# 2_waffling80-MX_matrix.net
KiCad netlist of a schematic drawn in Altium Designer
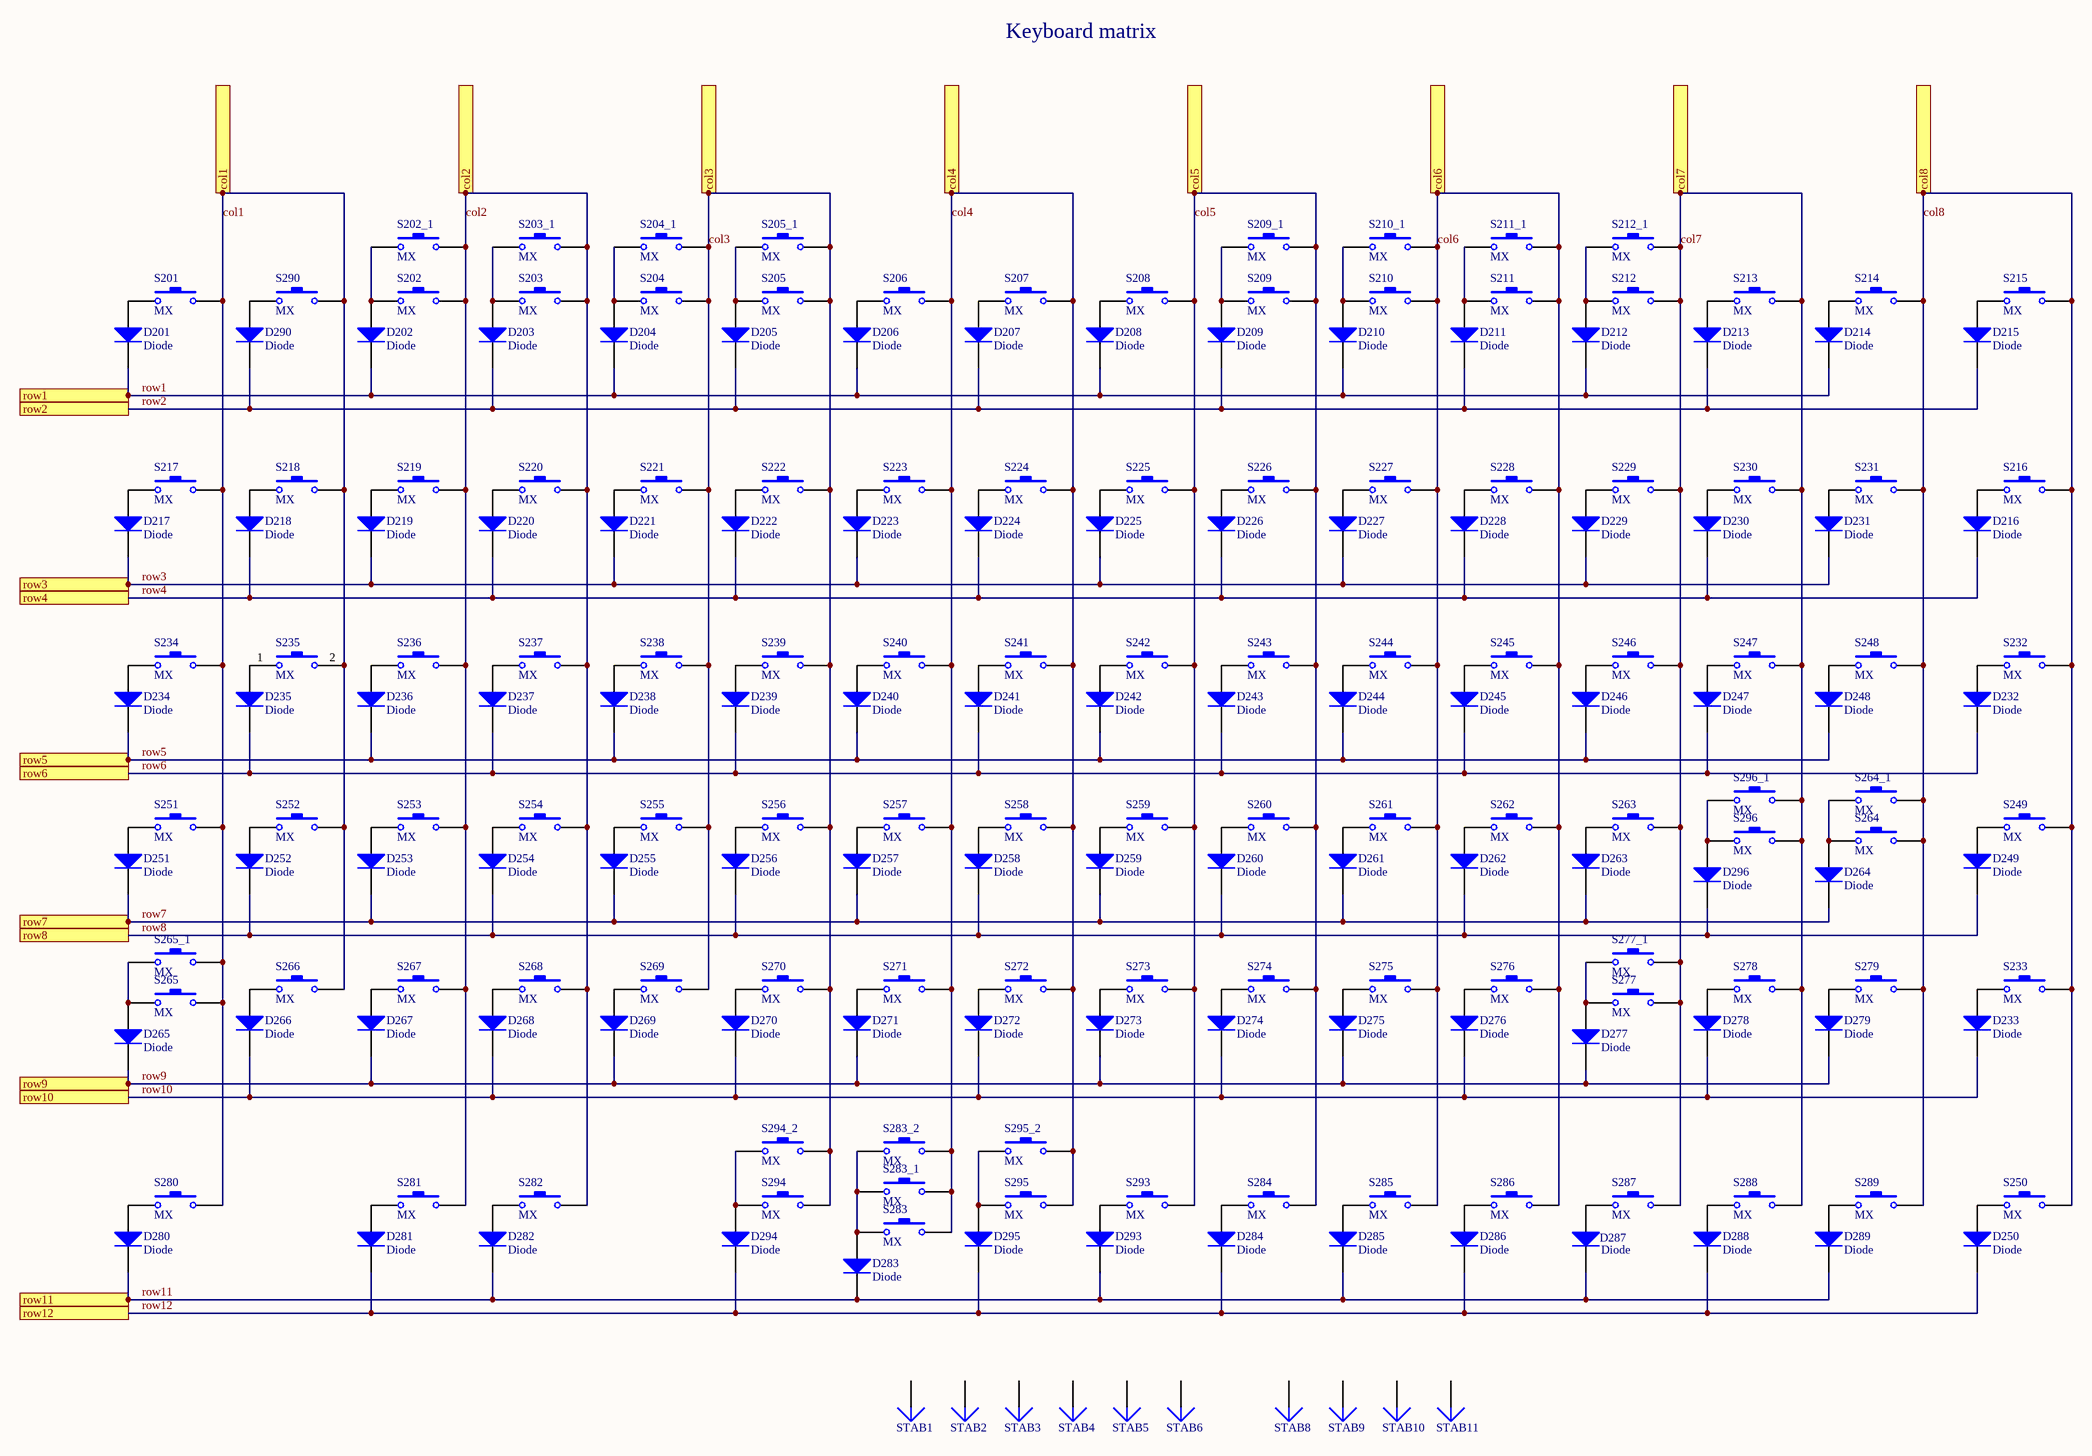
[diagram p0: 2_waffling80-MX_matrix.SchDoc]

(export (version "E")
  (design (tool "Eeschema 10.0.6"))
  (components
    (comp (ref "D201")
      (value "Diode")
      (footprint "SOD-123")
      (description "Default Diode")
      (fields (field (name "LCSC PART #") "C81598") (field (name "MRF.PART") "1N4148W"))
      (libsource (lib "Miscellaneous Devices") (part "Diode"))
    )
    (comp (ref "D202")
      (value "Diode")
      (footprint "SOD-123")
      (description "Default Diode")
      (fields (field (name "LCSC PART #") "C81598") (field (name "MRF.PART") "1N4148W"))
      (libsource (lib "Miscellaneous Devices") (part "Diode"))
    )
    (comp (ref "D203")
      (value "Diode")
      (footprint "SOD-123")
      (description "Default Diode")
      (fields (field (name "LCSC PART #") "C81598") (field (name "MRF.PART") "1N4148W"))
      (libsource (lib "Miscellaneous Devices") (part "Diode"))
    )
    (comp (ref "D204")
      (value "Diode")
      (footprint "SOD-123")
      (description "Default Diode")
      (fields (field (name "LCSC PART #") "C81598") (field (name "MRF.PART") "1N4148W"))
      (libsource (lib "Miscellaneous Devices") (part "Diode"))
    )
    (comp (ref "D205")
      (value "Diode")
      (footprint "SOD-123")
      (description "Default Diode")
      (fields (field (name "LCSC PART #") "C81598") (field (name "MRF.PART") "1N4148W"))
      (libsource (lib "Miscellaneous Devices") (part "Diode"))
    )
    (comp (ref "D206")
      (value "Diode")
      (footprint "SOD-123")
      (description "Default Diode")
      (fields (field (name "LCSC PART #") "C81598") (field (name "MRF.PART") "1N4148W"))
      (libsource (lib "Miscellaneous Devices") (part "Diode"))
    )
    (comp (ref "D207")
      (value "Diode")
      (footprint "SOD-123")
      (description "Default Diode")
      (fields (field (name "LCSC PART #") "C81598") (field (name "MRF.PART") "1N4148W"))
      (libsource (lib "Miscellaneous Devices") (part "Diode"))
    )
    (comp (ref "D208")
      (value "Diode")
      (footprint "SOD-123")
      (description "Default Diode")
      (fields (field (name "LCSC PART #") "C81598") (field (name "MRF.PART") "1N4148W"))
      (libsource (lib "Miscellaneous Devices") (part "Diode"))
    )
    (comp (ref "D209")
      (value "Diode")
      (footprint "SOD-123")
      (description "Default Diode")
      (fields (field (name "LCSC PART #") "C81598") (field (name "MRF.PART") "1N4148W"))
      (libsource (lib "Miscellaneous Devices") (part "Diode"))
    )
    (comp (ref "D210")
      (value "Diode")
      (footprint "SOD-123")
      (description "Default Diode")
      (fields (field (name "LCSC PART #") "C81598") (field (name "MRF.PART") "1N4148W"))
      (libsource (lib "Miscellaneous Devices") (part "Diode"))
    )
    (comp (ref "D211")
      (value "Diode")
      (footprint "SOD-123")
      (description "Default Diode")
      (fields (field (name "LCSC PART #") "C81598") (field (name "MRF.PART") "1N4148W"))
      (libsource (lib "Miscellaneous Devices") (part "Diode"))
    )
    (comp (ref "D212")
      (value "Diode")
      (footprint "SOD-123")
      (description "Default Diode")
      (fields (field (name "LCSC PART #") "C81598") (field (name "MRF.PART") "1N4148W"))
      (libsource (lib "Miscellaneous Devices") (part "Diode"))
    )
    (comp (ref "D213")
      (value "Diode")
      (footprint "SOD-123")
      (description "Default Diode")
      (fields (field (name "LCSC PART #") "C81598") (field (name "MRF.PART") "1N4148W"))
      (libsource (lib "Miscellaneous Devices") (part "Diode"))
    )
    (comp (ref "D214")
      (value "Diode")
      (footprint "SOD-123")
      (description "Default Diode")
      (fields (field (name "LCSC PART #") "C81598") (field (name "MRF.PART") "1N4148W"))
      (libsource (lib "Miscellaneous Devices") (part "Diode"))
    )
    (comp (ref "D215")
      (value "Diode")
      (footprint "SOD-123")
      (description "Default Diode")
      (fields (field (name "LCSC PART #") "C81598") (field (name "MRF.PART") "1N4148W"))
      (libsource (lib "Miscellaneous Devices") (part "Diode"))
    )
    (comp (ref "D216")
      (value "Diode")
      (footprint "SOD-123")
      (description "Default Diode")
      (fields (field (name "LCSC PART #") "C81598") (field (name "MRF.PART") "1N4148W"))
      (libsource (lib "Miscellaneous Devices") (part "Diode"))
    )
    (comp (ref "D217")
      (value "Diode")
      (footprint "SOD-123")
      (description "Default Diode")
      (fields (field (name "LCSC PART #") "C81598") (field (name "MRF.PART") "1N4148W"))
      (libsource (lib "Miscellaneous Devices") (part "Diode"))
    )
    (comp (ref "D218")
      (value "Diode")
      (footprint "SOD-123")
      (description "Default Diode")
      (fields (field (name "LCSC PART #") "C81598") (field (name "MRF.PART") "1N4148W"))
      (libsource (lib "Miscellaneous Devices") (part "Diode"))
    )
    (comp (ref "D219")
      (value "Diode")
      (footprint "SOD-123")
      (description "Default Diode")
      (fields (field (name "LCSC PART #") "C81598") (field (name "MRF.PART") "1N4148W"))
      (libsource (lib "Miscellaneous Devices") (part "Diode"))
    )
    (comp (ref "D220")
      (value "Diode")
      (footprint "SOD-123")
      (description "Default Diode")
      (fields (field (name "LCSC PART #") "C81598") (field (name "MRF.PART") "1N4148W"))
      (libsource (lib "Miscellaneous Devices") (part "Diode"))
    )
    (comp (ref "D221")
      (value "Diode")
      (footprint "SOD-123")
      (description "Default Diode")
      (fields (field (name "LCSC PART #") "C81598") (field (name "MRF.PART") "1N4148W"))
      (libsource (lib "Miscellaneous Devices") (part "Diode"))
    )
    (comp (ref "D222")
      (value "Diode")
      (footprint "SOD-123")
      (description "Default Diode")
      (fields (field (name "LCSC PART #") "C81598") (field (name "MRF.PART") "1N4148W"))
      (libsource (lib "Miscellaneous Devices") (part "Diode"))
    )
    (comp (ref "D223")
      (value "Diode")
      (footprint "SOD-123")
      (description "Default Diode")
      (fields (field (name "LCSC PART #") "C81598") (field (name "MRF.PART") "1N4148W"))
      (libsource (lib "Miscellaneous Devices") (part "Diode"))
    )
    (comp (ref "D224")
      (value "Diode")
      (footprint "SOD-123")
      (description "Default Diode")
      (fields (field (name "LCSC PART #") "C81598") (field (name "MRF.PART") "1N4148W"))
      (libsource (lib "Miscellaneous Devices") (part "Diode"))
    )
    (comp (ref "D225")
      (value "Diode")
      (footprint "SOD-123")
      (description "Default Diode")
      (fields (field (name "LCSC PART #") "C81598") (field (name "MRF.PART") "1N4148W"))
      (libsource (lib "Miscellaneous Devices") (part "Diode"))
    )
    (comp (ref "D226")
      (value "Diode")
      (footprint "SOD-123")
      (description "Default Diode")
      (fields (field (name "LCSC PART #") "C81598") (field (name "MRF.PART") "1N4148W"))
      (libsource (lib "Miscellaneous Devices") (part "Diode"))
    )
    (comp (ref "D227")
      (value "Diode")
      (footprint "SOD-123")
      (description "Default Diode")
      (fields (field (name "LCSC PART #") "C81598") (field (name "MRF.PART") "1N4148W"))
      (libsource (lib "Miscellaneous Devices") (part "Diode"))
    )
    (comp (ref "D228")
      (value "Diode")
      (footprint "SOD-123")
      (description "Default Diode")
      (fields (field (name "LCSC PART #") "C81598") (field (name "MRF.PART") "1N4148W"))
      (libsource (lib "Miscellaneous Devices") (part "Diode"))
    )
    (comp (ref "D229")
      (value "Diode")
      (footprint "SOD-123")
      (description "Default Diode")
      (fields (field (name "LCSC PART #") "C81598") (field (name "MRF.PART") "1N4148W"))
      (libsource (lib "Miscellaneous Devices") (part "Diode"))
    )
    (comp (ref "D230")
      (value "Diode")
      (footprint "SOD-123")
      (description "Default Diode")
      (fields (field (name "LCSC PART #") "C81598") (field (name "MRF.PART") "1N4148W"))
      (libsource (lib "Miscellaneous Devices") (part "Diode"))
    )
    (comp (ref "D231")
      (value "Diode")
      (footprint "SOD-123")
      (description "Default Diode")
      (fields (field (name "LCSC PART #") "C81598") (field (name "MRF.PART") "1N4148W"))
      (libsource (lib "Miscellaneous Devices") (part "Diode"))
    )
    (comp (ref "D232")
      (value "Diode")
      (footprint "SOD-123")
      (description "Default Diode")
      (fields (field (name "LCSC PART #") "C81598") (field (name "MRF.PART") "1N4148W"))
      (libsource (lib "Miscellaneous Devices") (part "Diode"))
    )
    (comp (ref "D233")
      (value "Diode")
      (footprint "SOD-123")
      (description "Default Diode")
      (fields (field (name "LCSC PART #") "C81598") (field (name "MRF.PART") "1N4148W"))
      (libsource (lib "Miscellaneous Devices") (part "Diode"))
    )
    (comp (ref "D234")
      (value "Diode")
      (footprint "SOD-123")
      (description "Default Diode")
      (fields (field (name "LCSC PART #") "C81598") (field (name "MRF.PART") "1N4148W"))
      (libsource (lib "Miscellaneous Devices") (part "Diode"))
    )
    (comp (ref "D235")
      (value "Diode")
      (footprint "SOD-123")
      (description "Default Diode")
      (fields (field (name "LCSC PART #") "C81598") (field (name "MRF.PART") "1N4148W"))
      (libsource (lib "Miscellaneous Devices") (part "Diode"))
    )
    (comp (ref "D236")
      (value "Diode")
      (footprint "SOD-123")
      (description "Default Diode")
      (fields (field (name "LCSC PART #") "C81598") (field (name "MRF.PART") "1N4148W"))
      (libsource (lib "Miscellaneous Devices") (part "Diode"))
    )
    (comp (ref "D237")
      (value "Diode")
      (footprint "SOD-123")
      (description "Default Diode")
      (fields (field (name "LCSC PART #") "C81598") (field (name "MRF.PART") "1N4148W"))
      (libsource (lib "Miscellaneous Devices") (part "Diode"))
    )
    (comp (ref "D238")
      (value "Diode")
      (footprint "SOD-123")
      (description "Default Diode")
      (fields (field (name "LCSC PART #") "C81598") (field (name "MRF.PART") "1N4148W"))
      (libsource (lib "Miscellaneous Devices") (part "Diode"))
    )
    (comp (ref "D239")
      (value "Diode")
      (footprint "SOD-123")
      (description "Default Diode")
      (fields (field (name "LCSC PART #") "C81598") (field (name "MRF.PART") "1N4148W"))
      (libsource (lib "Miscellaneous Devices") (part "Diode"))
    )
    (comp (ref "D240")
      (value "Diode")
      (footprint "SOD-123")
      (description "Default Diode")
      (fields (field (name "LCSC PART #") "C81598") (field (name "MRF.PART") "1N4148W"))
      (libsource (lib "Miscellaneous Devices") (part "Diode"))
    )
    (comp (ref "D241")
      (value "Diode")
      (footprint "SOD-123")
      (description "Default Diode")
      (fields (field (name "LCSC PART #") "C81598") (field (name "MRF.PART") "1N4148W"))
      (libsource (lib "Miscellaneous Devices") (part "Diode"))
    )
    (comp (ref "D242")
      (value "Diode")
      (footprint "SOD-123")
      (description "Default Diode")
      (fields (field (name "LCSC PART #") "C81598") (field (name "MRF.PART") "1N4148W"))
      (libsource (lib "Miscellaneous Devices") (part "Diode"))
    )
    (comp (ref "D243")
      (value "Diode")
      (footprint "SOD-123")
      (description "Default Diode")
      (fields (field (name "LCSC PART #") "C81598") (field (name "MRF.PART") "1N4148W"))
      (libsource (lib "Miscellaneous Devices") (part "Diode"))
    )
    (comp (ref "D244")
      (value "Diode")
      (footprint "SOD-123")
      (description "Default Diode")
      (fields (field (name "LCSC PART #") "C81598") (field (name "MRF.PART") "1N4148W"))
      (libsource (lib "Miscellaneous Devices") (part "Diode"))
    )
    (comp (ref "D245")
      (value "Diode")
      (footprint "SOD-123")
      (description "Default Diode")
      (fields (field (name "LCSC PART #") "C81598") (field (name "MRF.PART") "1N4148W"))
      (libsource (lib "Miscellaneous Devices") (part "Diode"))
    )
    (comp (ref "D246")
      (value "Diode")
      (footprint "SOD-123")
      (description "Default Diode")
      (fields (field (name "LCSC PART #") "C81598") (field (name "MRF.PART") "1N4148W"))
      (libsource (lib "Miscellaneous Devices") (part "Diode"))
    )
    (comp (ref "D247")
      (value "Diode")
      (footprint "SOD-123")
      (description "Default Diode")
      (fields (field (name "LCSC PART #") "C81598") (field (name "MRF.PART") "1N4148W"))
      (libsource (lib "Miscellaneous Devices") (part "Diode"))
    )
    (comp (ref "D248")
      (value "Diode")
      (footprint "SOD-123")
      (description "Default Diode")
      (fields (field (name "LCSC PART #") "C81598") (field (name "MRF.PART") "1N4148W"))
      (libsource (lib "Miscellaneous Devices") (part "Diode"))
    )
    (comp (ref "D249")
      (value "Diode")
      (footprint "SOD-123")
      (description "Default Diode")
      (fields (field (name "LCSC PART #") "C81598") (field (name "MRF.PART") "1N4148W"))
      (libsource (lib "Miscellaneous Devices") (part "Diode"))
    )
    (comp (ref "D250")
      (value "Diode")
      (footprint "SOD-123")
      (description "Default Diode")
      (fields (field (name "LCSC PART #") "C81598") (field (name "MRF.PART") "1N4148W"))
      (libsource (lib "Miscellaneous Devices") (part "Diode"))
    )
    (comp (ref "D251")
      (value "Diode")
      (footprint "SOD-123")
      (description "Default Diode")
      (fields (field (name "LCSC PART #") "C81598") (field (name "MRF.PART") "1N4148W"))
      (libsource (lib "Miscellaneous Devices") (part "Diode"))
    )
    (comp (ref "D252")
      (value "Diode")
      (footprint "SOD-123")
      (description "Default Diode")
      (fields (field (name "LCSC PART #") "C81598") (field (name "MRF.PART") "1N4148W"))
      (libsource (lib "Miscellaneous Devices") (part "Diode"))
    )
    (comp (ref "D253")
      (value "Diode")
      (footprint "SOD-123")
      (description "Default Diode")
      (fields (field (name "LCSC PART #") "C81598") (field (name "MRF.PART") "1N4148W"))
      (libsource (lib "Miscellaneous Devices") (part "Diode"))
    )
    (comp (ref "D254")
      (value "Diode")
      (footprint "SOD-123")
      (description "Default Diode")
      (fields (field (name "LCSC PART #") "C81598") (field (name "MRF.PART") "1N4148W"))
      (libsource (lib "Miscellaneous Devices") (part "Diode"))
    )
    (comp (ref "D255")
      (value "Diode")
      (footprint "SOD-123")
      (description "Default Diode")
      (fields (field (name "LCSC PART #") "C81598") (field (name "MRF.PART") "1N4148W"))
      (libsource (lib "Miscellaneous Devices") (part "Diode"))
    )
    (comp (ref "D256")
      (value "Diode")
      (footprint "SOD-123")
      (description "Default Diode")
      (fields (field (name "LCSC PART #") "C81598") (field (name "MRF.PART") "1N4148W"))
      (libsource (lib "Miscellaneous Devices") (part "Diode"))
    )
    (comp (ref "D257")
      (value "Diode")
      (footprint "SOD-123")
      (description "Default Diode")
      (fields (field (name "LCSC PART #") "C81598") (field (name "MRF.PART") "1N4148W"))
      (libsource (lib "Miscellaneous Devices") (part "Diode"))
    )
    (comp (ref "D258")
      (value "Diode")
      (footprint "SOD-123")
      (description "Default Diode")
      (fields (field (name "LCSC PART #") "C81598") (field (name "MRF.PART") "1N4148W"))
      (libsource (lib "Miscellaneous Devices") (part "Diode"))
    )
    (comp (ref "D259")
      (value "Diode")
      (footprint "SOD-123")
      (description "Default Diode")
      (fields (field (name "LCSC PART #") "C81598") (field (name "MRF.PART") "1N4148W"))
      (libsource (lib "Miscellaneous Devices") (part "Diode"))
    )
    (comp (ref "D260")
      (value "Diode")
      (footprint "SOD-123")
      (description "Default Diode")
      (fields (field (name "LCSC PART #") "C81598") (field (name "MRF.PART") "1N4148W"))
      (libsource (lib "Miscellaneous Devices") (part "Diode"))
    )
    (comp (ref "D261")
      (value "Diode")
      (footprint "SOD-123")
      (description "Default Diode")
      (fields (field (name "LCSC PART #") "C81598") (field (name "MRF.PART") "1N4148W"))
      (libsource (lib "Miscellaneous Devices") (part "Diode"))
    )
    (comp (ref "D262")
      (value "Diode")
      (footprint "SOD-123")
      (description "Default Diode")
      (fields (field (name "LCSC PART #") "C81598") (field (name "MRF.PART") "1N4148W"))
      (libsource (lib "Miscellaneous Devices") (part "Diode"))
    )
    (comp (ref "D263")
      (value "Diode")
      (footprint "SOD-123")
      (description "Default Diode")
      (fields (field (name "LCSC PART #") "C81598") (field (name "MRF.PART") "1N4148W"))
      (libsource (lib "Miscellaneous Devices") (part "Diode"))
    )
    (comp (ref "D264")
      (value "Diode")
      (footprint "SOD-123")
      (description "Default Diode")
      (fields (field (name "LCSC PART #") "C81598") (field (name "MRF.PART") "1N4148W"))
      (libsource (lib "Miscellaneous Devices") (part "Diode"))
    )
    (comp (ref "D265")
      (value "Diode")
      (footprint "SOD-123")
      (description "Default Diode")
      (fields (field (name "LCSC PART #") "C81598") (field (name "MRF.PART") "1N4148W"))
      (libsource (lib "Miscellaneous Devices") (part "Diode"))
    )
    (comp (ref "D266")
      (value "Diode")
      (footprint "SOD-123")
      (description "Default Diode")
      (fields (field (name "LCSC PART #") "C81598") (field (name "MRF.PART") "1N4148W"))
      (libsource (lib "Miscellaneous Devices") (part "Diode"))
    )
    (comp (ref "D267")
      (value "Diode")
      (footprint "SOD-123")
      (description "Default Diode")
      (fields (field (name "LCSC PART #") "C81598") (field (name "MRF.PART") "1N4148W"))
      (libsource (lib "Miscellaneous Devices") (part "Diode"))
    )
    (comp (ref "D268")
      (value "Diode")
      (footprint "SOD-123")
      (description "Default Diode")
      (fields (field (name "LCSC PART #") "C81598") (field (name "MRF.PART") "1N4148W"))
      (libsource (lib "Miscellaneous Devices") (part "Diode"))
    )
    (comp (ref "D269")
      (value "Diode")
      (footprint "SOD-123")
      (description "Default Diode")
      (fields (field (name "LCSC PART #") "C81598") (field (name "MRF.PART") "1N4148W"))
      (libsource (lib "Miscellaneous Devices") (part "Diode"))
    )
    (comp (ref "D270")
      (value "Diode")
      (footprint "SOD-123")
      (description "Default Diode")
      (fields (field (name "LCSC PART #") "C81598") (field (name "MRF.PART") "1N4148W"))
      (libsource (lib "Miscellaneous Devices") (part "Diode"))
    )
    (comp (ref "D271")
      (value "Diode")
      (footprint "SOD-123")
      (description "Default Diode")
      (fields (field (name "LCSC PART #") "C81598") (field (name "MRF.PART") "1N4148W"))
      (libsource (lib "Miscellaneous Devices") (part "Diode"))
    )
    (comp (ref "D272")
      (value "Diode")
      (footprint "SOD-123")
      (description "Default Diode")
      (fields (field (name "LCSC PART #") "C81598") (field (name "MRF.PART") "1N4148W"))
      (libsource (lib "Miscellaneous Devices") (part "Diode"))
    )
    (comp (ref "D273")
      (value "Diode")
      (footprint "SOD-123")
      (description "Default Diode")
      (fields (field (name "LCSC PART #") "C81598") (field (name "MRF.PART") "1N4148W"))
      (libsource (lib "Miscellaneous Devices") (part "Diode"))
    )
    (comp (ref "D274")
      (value "Diode")
      (footprint "SOD-123")
      (description "Default Diode")
      (fields (field (name "LCSC PART #") "C81598") (field (name "MRF.PART") "1N4148W"))
      (libsource (lib "Miscellaneous Devices") (part "Diode"))
    )
    (comp (ref "D275")
      (value "Diode")
      (footprint "SOD-123")
      (description "Default Diode")
      (fields (field (name "LCSC PART #") "C81598") (field (name "MRF.PART") "1N4148W"))
      (libsource (lib "Miscellaneous Devices") (part "Diode"))
    )
    (comp (ref "D276")
      (value "Diode")
      (footprint "SOD-123")
      (description "Default Diode")
      (fields (field (name "LCSC PART #") "C81598") (field (name "MRF.PART") "1N4148W"))
      (libsource (lib "Miscellaneous Devices") (part "Diode"))
    )
    (comp (ref "D277")
      (value "Diode")
      (footprint "SOD-123")
      (description "Default Diode")
      (fields (field (name "LCSC PART #") "C81598") (field (name "MRF.PART") "1N4148W"))
      (libsource (lib "Miscellaneous Devices") (part "Diode"))
    )
    (comp (ref "D278")
      (value "Diode")
      (footprint "SOD-123")
      (description "Default Diode")
      (fields (field (name "LCSC PART #") "C81598") (field (name "MRF.PART") "1N4148W"))
      (libsource (lib "Miscellaneous Devices") (part "Diode"))
    )
    (comp (ref "D279")
      (value "Diode")
      (footprint "SOD-123")
      (description "Default Diode")
      (fields (field (name "LCSC PART #") "C81598") (field (name "MRF.PART") "1N4148W"))
      (libsource (lib "Miscellaneous Devices") (part "Diode"))
    )
    (comp (ref "D280")
      (value "Diode")
      (footprint "SOD-123")
      (description "Default Diode")
      (fields (field (name "LCSC PART #") "C81598") (field (name "MRF.PART") "1N4148W"))
      (libsource (lib "Miscellaneous Devices") (part "Diode"))
    )
    (comp (ref "D281")
      (value "Diode")
      (footprint "SOD-123")
      (description "Default Diode")
      (fields (field (name "LCSC PART #") "C81598") (field (name "MRF.PART") "1N4148W"))
      (libsource (lib "Miscellaneous Devices") (part "Diode"))
    )
    (comp (ref "D282")
      (value "Diode")
      (footprint "SOD-123")
      (description "Default Diode")
      (fields (field (name "LCSC PART #") "C81598") (field (name "MRF.PART") "1N4148W"))
      (libsource (lib "Miscellaneous Devices") (part "Diode"))
    )
    (comp (ref "D283")
      (value "Diode")
      (footprint "SOD-123")
      (description "Default Diode")
      (fields (field (name "LCSC PART #") "C81598") (field (name "MRF.PART") "1N4148W"))
      (libsource (lib "Miscellaneous Devices") (part "Diode"))
    )
    (comp (ref "D284")
      (value "Diode")
      (footprint "SOD-123")
      (description "Default Diode")
      (fields (field (name "LCSC PART #") "C81598") (field (name "MRF.PART") "1N4148W"))
      (libsource (lib "Miscellaneous Devices") (part "Diode"))
    )
    (comp (ref "D285")
      (value "Diode")
      (footprint "SOD-123")
      (description "Default Diode")
      (fields (field (name "LCSC PART #") "C81598") (field (name "MRF.PART") "1N4148W"))
      (libsource (lib "Miscellaneous Devices") (part "Diode"))
    )
    (comp (ref "D286")
      (value "Diode")
      (footprint "SOD-123")
      (description "Default Diode")
      (fields (field (name "LCSC PART #") "C81598") (field (name "MRF.PART") "1N4148W"))
      (libsource (lib "Miscellaneous Devices") (part "Diode"))
    )
    (comp (ref "D287")
      (value "Diode")
      (footprint "SOD-123")
      (description "Default Diode")
      (fields (field (name "LCSC PART #") "C81598") (field (name "MRF.PART") "1N4148W"))
      (libsource (lib "Miscellaneous Devices") (part "Diode"))
    )
    (comp (ref "D288")
      (value "Diode")
      (footprint "SOD-123")
      (description "Default Diode")
      (fields (field (name "LCSC PART #") "C81598") (field (name "MRF.PART") "1N4148W"))
      (libsource (lib "Miscellaneous Devices") (part "Diode"))
    )
    (comp (ref "D289")
      (value "Diode")
      (footprint "SOD-123")
      (description "Default Diode")
      (fields (field (name "LCSC PART #") "C81598") (field (name "MRF.PART") "1N4148W"))
      (libsource (lib "Miscellaneous Devices") (part "Diode"))
    )
    (comp (ref "D290")
      (value "Diode")
      (footprint "SOD-123")
      (description "Default Diode")
      (fields (field (name "LCSC PART #") "C81598") (field (name "MRF.PART") "1N4148W"))
      (libsource (lib "Miscellaneous Devices") (part "Diode"))
    )
    (comp (ref "D293")
      (value "Diode")
      (footprint "SOD-123")
      (description "Default Diode")
      (fields (field (name "LCSC PART #") "C81598") (field (name "MRF.PART") "1N4148W"))
      (libsource (lib "Miscellaneous Devices") (part "Diode"))
    )
    (comp (ref "D294")
      (value "Diode")
      (footprint "SOD-123")
      (description "Default Diode")
      (fields (field (name "LCSC PART #") "C81598") (field (name "MRF.PART") "1N4148W"))
      (libsource (lib "Miscellaneous Devices") (part "Diode"))
    )
    (comp (ref "D295")
      (value "Diode")
      (footprint "SOD-123")
      (description "Default Diode")
      (fields (field (name "LCSC PART #") "C81598") (field (name "MRF.PART") "1N4148W"))
      (libsource (lib "Miscellaneous Devices") (part "Diode"))
    )
    (comp (ref "D296")
      (value "Diode")
      (footprint "SOD-123")
      (description "Default Diode")
      (fields (field (name "LCSC PART #") "C81598") (field (name "MRF.PART") "1N4148W"))
      (libsource (lib "Miscellaneous Devices") (part "Diode"))
    )
    (comp (ref "S201")
      (value "MX")
      (footprint "MX-switch - switched pol")
      (description "Switch")
      (libsource (lib "Miscellaneous Devices") (part "SW-PB"))
    )
    (comp (ref "S202")
      (value "MX")
      (footprint "MX-switch - switched pol")
      (description "Switch")
      (libsource (lib "Miscellaneous Devices") (part "SW-PB"))
    )
    (comp (ref "S202_1")
      (value "MX")
      (footprint "MX-switch")
      (description "Switch")
      (libsource (lib "Miscellaneous Devices") (part "SW-PB"))
    )
    (comp (ref "S203")
      (value "MX")
      (footprint "MX-switch - switched pol")
      (description "Switch")
      (libsource (lib "Miscellaneous Devices") (part "SW-PB"))
    )
    (comp (ref "S203_1")
      (value "MX")
      (footprint "MX-switch")
      (description "Switch")
      (libsource (lib "Miscellaneous Devices") (part "SW-PB"))
    )
    (comp (ref "S204")
      (value "MX")
      (footprint "MX-switch - switched pol")
      (description "Switch")
      (libsource (lib "Miscellaneous Devices") (part "SW-PB"))
    )
    (comp (ref "S204_1")
      (value "MX")
      (footprint "MX-switch")
      (description "Switch")
      (libsource (lib "Miscellaneous Devices") (part "SW-PB"))
    )
    (comp (ref "S205")
      (value "MX")
      (footprint "MX-switch - switched pol")
      (description "Switch")
      (libsource (lib "Miscellaneous Devices") (part "SW-PB"))
    )
    (comp (ref "S205_1")
      (value "MX")
      (footprint "MX-switch")
      (description "Switch")
      (libsource (lib "Miscellaneous Devices") (part "SW-PB"))
    )
    (comp (ref "S206")
      (value "MX")
      (footprint "MX-switch")
      (description "Switch")
      (libsource (lib "Miscellaneous Devices") (part "SW-PB"))
    )
    (comp (ref "S207")
      (value "MX")
      (footprint "MX-switch")
      (description "Switch")
      (libsource (lib "Miscellaneous Devices") (part "SW-PB"))
    )
    (comp (ref "S208")
      (value "MX")
      (footprint "MX-switch")
      (description "Switch")
      (libsource (lib "Miscellaneous Devices") (part "SW-PB"))
    )
    (comp (ref "S209")
      (value "MX")
      (footprint "MX-switch - switched pol")
      (description "Switch")
      (libsource (lib "Miscellaneous Devices") (part "SW-PB"))
    )
    (comp (ref "S209_1")
      (value "MX")
      (footprint "MX-switch")
      (description "Switch")
      (libsource (lib "Miscellaneous Devices") (part "SW-PB"))
    )
    (comp (ref "S210")
      (value "MX")
      (footprint "MX-switch")
      (description "Switch")
      (libsource (lib "Miscellaneous Devices") (part "SW-PB"))
    )
    (comp (ref "S210_1")
      (value "MX")
      (footprint "MX-switch - switched pol")
      (description "Switch")
      (libsource (lib "Miscellaneous Devices") (part "SW-PB"))
    )
    (comp (ref "S211")
      (value "MX")
      (footprint "MX-switch")
      (description "Switch")
      (libsource (lib "Miscellaneous Devices") (part "SW-PB"))
    )
    (comp (ref "S211_1")
      (value "MX")
      (footprint "MX-switch - switched pol")
      (description "Switch")
      (libsource (lib "Miscellaneous Devices") (part "SW-PB"))
    )
    (comp (ref "S212")
      (value "MX")
      (footprint "MX-switch")
      (description "Switch")
      (libsource (lib "Miscellaneous Devices") (part "SW-PB"))
    )
    (comp (ref "S212_1")
      (value "MX")
      (footprint "MX-switch - switched pol")
      (description "Switch")
      (libsource (lib "Miscellaneous Devices") (part "SW-PB"))
    )
    (comp (ref "S213")
      (value "MX")
      (footprint "MX-switch")
      (description "Switch")
      (libsource (lib "Miscellaneous Devices") (part "SW-PB"))
    )
    (comp (ref "S214")
      (value "MX")
      (footprint "MX-switch - switched pol")
      (description "Switch")
      (libsource (lib "Miscellaneous Devices") (part "SW-PB"))
    )
    (comp (ref "S215")
      (value "MX")
      (footprint "MX-switch")
      (description "Switch")
      (libsource (lib "Miscellaneous Devices") (part "SW-PB"))
    )
    (comp (ref "S216")
      (value "MX")
      (footprint "MX-switch")
      (description "Switch")
      (libsource (lib "Miscellaneous Devices") (part "SW-PB"))
    )
    (comp (ref "S217")
      (value "MX")
      (footprint "MX-switch - switched pol")
      (description "Switch")
      (libsource (lib "Miscellaneous Devices") (part "SW-PB"))
    )
    (comp (ref "S218")
      (value "MX")
      (footprint "MX-switch - switched pol")
      (description "Switch")
      (libsource (lib "Miscellaneous Devices") (part "SW-PB"))
    )
    (comp (ref "S219")
      (value "MX")
      (footprint "MX-switch - switched pol")
      (description "Switch")
      (libsource (lib "Miscellaneous Devices") (part "SW-PB"))
    )
    (comp (ref "S220")
      (value "MX")
      (footprint "MX-switch - switched pol")
      (description "Switch")
      (libsource (lib "Miscellaneous Devices") (part "SW-PB"))
    )
    (comp (ref "S221")
      (value "MX")
      (footprint "MX-switch - switched pol")
      (description "Switch")
      (libsource (lib "Miscellaneous Devices") (part "SW-PB"))
    )
    (comp (ref "S222")
      (value "MX")
      (footprint "MX-switch - switched pol")
      (description "Switch")
      (libsource (lib "Miscellaneous Devices") (part "SW-PB"))
    )
    (comp (ref "S223")
      (value "MX")
      (footprint "MX-switch - switched pol")
      (description "Switch")
      (libsource (lib "Miscellaneous Devices") (part "SW-PB"))
    )
    (comp (ref "S224")
      (value "MX")
      (footprint "MX-switch - switched pol")
      (description "Switch")
      (libsource (lib "Miscellaneous Devices") (part "SW-PB"))
    )
    (comp (ref "S225")
      (value "MX")
      (footprint "MX-switch - switched pol")
      (description "Switch")
      (libsource (lib "Miscellaneous Devices") (part "SW-PB"))
    )
    (comp (ref "S226")
      (value "MX")
      (footprint "MX-switch - switched pol")
      (description "Switch")
      (libsource (lib "Miscellaneous Devices") (part "SW-PB"))
    )
    (comp (ref "S227")
      (value "MX")
      (footprint "MX-switch - switched pol")
      (description "Switch")
      (libsource (lib "Miscellaneous Devices") (part "SW-PB"))
    )
    (comp (ref "S228")
      (value "MX")
      (footprint "MX-switch - switched pol")
      (description "Switch")
      (libsource (lib "Miscellaneous Devices") (part "SW-PB"))
    )
    (comp (ref "S229")
      (value "MX")
      (footprint "MX-switch - switched pol")
      (description "Switch")
      (libsource (lib "Miscellaneous Devices") (part "SW-PB"))
    )
    (comp (ref "S230")
      (value "MX")
      (footprint "MX-switch")
      (description "Switch")
      (libsource (lib "Miscellaneous Devices") (part "SW-PB"))
    )
    (comp (ref "S231")
      (value "MX")
      (footprint "MX-switch")
      (description "Switch")
      (libsource (lib "Miscellaneous Devices") (part "SW-PB"))
    )
    (comp (ref "S232")
      (value "MX")
      (footprint "MX-switch")
      (description "Switch")
      (libsource (lib "Miscellaneous Devices") (part "SW-PB"))
    )
    (comp (ref "S233")
      (value "MX")
      (footprint "MX-switch")
      (description "Switch")
      (libsource (lib "Miscellaneous Devices") (part "SW-PB"))
    )
    (comp (ref "S234")
      (value "MX")
      (footprint "MX-switch - switched pol")
      (description "TAB")
      (libsource (lib "Miscellaneous Devices") (part "SW-PB"))
    )
    (comp (ref "S235")
      (value "MX")
      (footprint "MX-switch - switched pol")
      (description "Switch")
      (libsource (lib "") (part "SW-PB_1"))
    )
    (comp (ref "S236")
      (value "MX")
      (footprint "MX-switch - switched pol")
      (description "Switch")
      (libsource (lib "Miscellaneous Devices") (part "SW-PB"))
    )
    (comp (ref "S237")
      (value "MX")
      (footprint "MX-switch - switched pol")
      (description "Switch")
      (libsource (lib "Miscellaneous Devices") (part "SW-PB"))
    )
    (comp (ref "S238")
      (value "MX")
      (footprint "MX-switch - switched pol")
      (description "Switch")
      (libsource (lib "Miscellaneous Devices") (part "SW-PB"))
    )
    (comp (ref "S239")
      (value "MX")
      (footprint "MX-switch - switched pol")
      (description "Switch")
      (libsource (lib "Miscellaneous Devices") (part "SW-PB"))
    )
    (comp (ref "S240")
      (value "MX")
      (footprint "MX-switch - switched pol")
      (description "Switch")
      (libsource (lib "Miscellaneous Devices") (part "SW-PB"))
    )
    (comp (ref "S241")
      (value "MX")
      (footprint "MX-switch - switched pol")
      (description "Switch")
      (libsource (lib "Miscellaneous Devices") (part "SW-PB"))
    )
    (comp (ref "S242")
      (value "MX")
      (footprint "MX-switch - switched pol")
      (description "Switch")
      (libsource (lib "Miscellaneous Devices") (part "SW-PB"))
    )
    (comp (ref "S243")
      (value "MX")
      (footprint "MX-switch - switched pol")
      (description "Switch")
      (libsource (lib "Miscellaneous Devices") (part "SW-PB"))
    )
    (comp (ref "S244")
      (value "MX")
      (footprint "MX-switch - switched pol")
      (description "Switch")
      (libsource (lib "Miscellaneous Devices") (part "SW-PB"))
    )
    (comp (ref "S245")
      (value "MX")
      (footprint "MX-switch - switched pol")
      (description "Switch")
      (libsource (lib "Miscellaneous Devices") (part "SW-PB"))
    )
    (comp (ref "S246")
      (value "MX")
      (footprint "MX-switch - switched pol")
      (description "Switch")
      (libsource (lib "Miscellaneous Devices") (part "SW-PB"))
    )
    (comp (ref "S247")
      (value "MX")
      (footprint "MX-switch - 1.5U")
      (description "Switch")
      (libsource (lib "Miscellaneous Devices") (part "SW-PB"))
    )
    (comp (ref "S248")
      (value "MX")
      (footprint "MX-switch")
      (description "Switch")
      (libsource (lib "Miscellaneous Devices") (part "SW-PB"))
    )
    (comp (ref "S249")
      (value "MX")
      (footprint "MX-switch")
      (description "Switch")
      (libsource (lib "Miscellaneous Devices") (part "SW-PB"))
    )
    (comp (ref "S250")
      (value "MX")
      (footprint "MX-switch")
      (description "Switch")
      (libsource (lib "Miscellaneous Devices") (part "SW-PB"))
    )
    (comp (ref "S251")
      (value "MX")
      (footprint "MX-switch - CAPS")
      (description "Switch")
      (libsource (lib "Miscellaneous Devices") (part "SW-PB"))
    )
    (comp (ref "S252")
      (value "MX")
      (footprint "MX-switch - switched pol")
      (description "Switch")
      (libsource (lib "Miscellaneous Devices") (part "SW-PB"))
    )
    (comp (ref "S253")
      (value "MX")
      (footprint "MX-switch - switched pol")
      (description "Switch")
      (libsource (lib "Miscellaneous Devices") (part "SW-PB"))
    )
    (comp (ref "S254")
      (value "MX")
      (footprint "MX-switch - switched pol")
      (description "Switch")
      (libsource (lib "Miscellaneous Devices") (part "SW-PB"))
    )
    (comp (ref "S255")
      (value "MX")
      (footprint "MX-switch - switched pol")
      (description "Switch")
      (libsource (lib "Miscellaneous Devices") (part "SW-PB"))
    )
    (comp (ref "S256")
      (value "MX")
      (footprint "MX-switch - switched pol")
      (description "Switch")
      (libsource (lib "Miscellaneous Devices") (part "SW-PB"))
    )
    (comp (ref "S257")
      (value "MX")
      (footprint "MX-switch - switched pol")
      (description "Switch")
      (libsource (lib "Miscellaneous Devices") (part "SW-PB"))
    )
    (comp (ref "S258")
      (value "MX")
      (footprint "MX-switch - switched pol")
      (description "Switch")
      (libsource (lib "Miscellaneous Devices") (part "SW-PB"))
    )
    (comp (ref "S259")
      (value "MX")
      (footprint "MX-switch - switched pol")
      (description "Switch")
      (libsource (lib "Miscellaneous Devices") (part "SW-PB"))
    )
    (comp (ref "S260")
      (value "MX")
      (footprint "MX-switch - switched pol")
      (description "Switch")
      (libsource (lib "Miscellaneous Devices") (part "SW-PB"))
    )
    (comp (ref "S261")
      (value "MX")
      (footprint "MX-switch")
      (description "Switch")
      (libsource (lib "Miscellaneous Devices") (part "SW-PB"))
    )
    (comp (ref "S262")
      (value "MX")
      (footprint "MX-switch - switched pol")
      (description "Switch")
      (libsource (lib "Miscellaneous Devices") (part "SW-PB"))
    )
    (comp (ref "S263")
      (value "MX")
      (footprint "MX-switch")
      (description "Switch")
      (libsource (lib "Miscellaneous Devices") (part "SW-PB"))
    )
    (comp (ref "S264")
      (value "MX")
      (footprint "MX-switch - switched pol")
      (description "Switch")
      (libsource (lib "Miscellaneous Devices") (part "SW-PB"))
    )
    (comp (ref "S264_1")
      (value "MX")
      (footprint "MX-switch")
      (description "Switch")
      (libsource (lib "Miscellaneous Devices") (part "SW-PB"))
    )
    (comp (ref "S265")
      (value "MX")
      (footprint "MX-switch - switched pol")
      (description "Switch")
      (libsource (lib "Miscellaneous Devices") (part "SW-PB"))
    )
    (comp (ref "S265_1")
      (value "MX")
      (footprint "MX-switch")
      (description "Switch")
      (libsource (lib "Miscellaneous Devices") (part "SW-PB"))
    )
    (comp (ref "S266")
      (value "MX")
      (footprint "MX-switch - switched pol")
      (description "Switch")
      (libsource (lib "Miscellaneous Devices") (part "SW-PB"))
    )
    (comp (ref "S267")
      (value "MX")
      (footprint "MX-switch - switched pol")
      (description "Switch")
      (libsource (lib "Miscellaneous Devices") (part "SW-PB"))
    )
    (comp (ref "S268")
      (value "MX")
      (footprint "MX-switch - switched pol")
      (description "Switch")
      (libsource (lib "Miscellaneous Devices") (part "SW-PB"))
    )
    (comp (ref "S269")
      (value "MX")
      (footprint "MX-switch - switched pol")
      (description "Switch")
      (libsource (lib "Miscellaneous Devices") (part "SW-PB"))
    )
    (comp (ref "S270")
      (value "MX")
      (footprint "MX-switch - switched pol")
      (description "Switch")
      (libsource (lib "Miscellaneous Devices") (part "SW-PB"))
    )
    (comp (ref "S271")
      (value "MX")
      (footprint "MX-switch - switched pol")
      (description "Switch")
      (libsource (lib "Miscellaneous Devices") (part "SW-PB"))
    )
    (comp (ref "S272")
      (value "MX")
      (footprint "MX-switch - switched pol")
      (description "Switch")
      (libsource (lib "Miscellaneous Devices") (part "SW-PB"))
    )
    (comp (ref "S273")
      (value "MX")
      (footprint "MX-switch - switched pol")
      (description "Switch")
      (libsource (lib "Miscellaneous Devices") (part "SW-PB"))
    )
    (comp (ref "S274")
      (value "MX")
      (footprint "MX-switch - switched pol")
      (description "Switch")
      (libsource (lib "Miscellaneous Devices") (part "SW-PB"))
    )
    (comp (ref "S275")
      (value "MX")
      (footprint "MX-switch - switched pol")
      (description "Switch")
      (libsource (lib "Miscellaneous Devices") (part "SW-PB"))
    )
    (comp (ref "S276")
      (value "MX")
      (footprint "MX-switch - switched pol")
      (description "Switch")
      (libsource (lib "Miscellaneous Devices") (part "SW-PB"))
    )
    (comp (ref "S277")
      (value "MX")
      (footprint "MX-switch - switched pol")
      (description "Switch")
      (libsource (lib "Miscellaneous Devices") (part "SW-PB"))
    )
    (comp (ref "S277_1")
      (value "MX")
      (footprint "MX-switch")
      (description "Switch")
      (libsource (lib "Miscellaneous Devices") (part "SW-PB"))
    )
    (comp (ref "S278")
      (value "MX")
      (footprint "MX-switch - switched pol")
      (description "Switch")
      (libsource (lib "Miscellaneous Devices") (part "SW-PB"))
    )
    (comp (ref "S279")
      (value "MX")
      (footprint "MX-switch")
      (description "Switch")
      (libsource (lib "Miscellaneous Devices") (part "SW-PB"))
    )
    (comp (ref "S280")
      (value "MX")
      (footprint "MX-switch - 1.5u MOD-L")
      (description "Switch")
      (libsource (lib "Miscellaneous Devices") (part "SW-PB"))
    )
    (comp (ref "S281")
      (value "MX")
      (footprint "MX-switch - 1u MOD-L")
      (description "Switch")
      (libsource (lib "Miscellaneous Devices") (part "SW-PB"))
    )
    (comp (ref "S282")
      (value "MX")
      (footprint "MX-switch - 1.5u MOD-L")
      (description "Switch")
      (libsource (lib "Miscellaneous Devices") (part "SW-PB"))
    )
    (comp (ref "S283")
      (value "MX")
      (footprint "MX-switch")
      (description "Switch")
      (libsource (lib "Miscellaneous Devices") (part "SW-PB"))
    )
    (comp (ref "S283_1")
      (value "MX")
      (footprint "MX-switch")
      (description "Switch")
      (libsource (lib "Miscellaneous Devices") (part "SW-PB"))
    )
    (comp (ref "S283_2")
      (value "MX")
      (footprint "MX-switch - switched pol")
      (description "Switch")
      (libsource (lib "Miscellaneous Devices") (part "SW-PB"))
    )
    (comp (ref "S284")
      (value "MX")
      (footprint "MX-switch - 1.5u MOD-R")
      (description "Switch")
      (libsource (lib "Miscellaneous Devices") (part "SW-PB"))
    )
    (comp (ref "S285")
      (value "MX")
      (footprint "MX-switch - 1u MOD-R")
      (description "Switch")
      (libsource (lib "Miscellaneous Devices") (part "SW-PB"))
    )
    (comp (ref "S286")
      (value "MX")
      (footprint "MX-switch - 1.5u MOD-R")
      (description "Switch")
      (libsource (lib "Miscellaneous Devices") (part "SW-PB"))
    )
    (comp (ref "S287")
      (value "MX")
      (footprint "MX-switch")
      (description "Switch")
      (libsource (lib "Miscellaneous Devices") (part "SW-PB"))
    )
    (comp (ref "S288")
      (value "MX")
      (footprint "MX-switch")
      (description "Switch")
      (libsource (lib "Miscellaneous Devices") (part "SW-PB"))
    )
    (comp (ref "S289")
      (value "MX")
      (footprint "MX-switch")
      (description "Switch")
      (libsource (lib "Miscellaneous Devices") (part "SW-PB"))
    )
    (comp (ref "S290")
      (value "MX")
      (footprint "MX-switch")
      (description "Switch")
      (libsource (lib "Miscellaneous Devices") (part "SW-PB"))
    )
    (comp (ref "S293")
      (value "MX")
      (footprint "MX-switch")
      (description "Switch")
      (libsource (lib "Miscellaneous Devices") (part "SW-PB"))
    )
    (comp (ref "S294")
      (value "MX")
      (footprint "MX-switch")
      (description "Switch")
      (libsource (lib "Miscellaneous Devices") (part "SW-PB"))
    )
    (comp (ref "S294_2")
      (value "MX")
      (footprint "MX-switch")
      (description "Switch")
      (libsource (lib "Miscellaneous Devices") (part "SW-PB"))
    )
    (comp (ref "S295")
      (value "MX")
      (footprint "MX-switch")
      (description "Switch")
      (libsource (lib "Miscellaneous Devices") (part "SW-PB"))
    )
    (comp (ref "S295_2")
      (value "MX")
      (footprint "MX-switch")
      (description "Switch")
      (libsource (lib "Miscellaneous Devices") (part "SW-PB"))
    )
    (comp (ref "S296")
      (value "MX")
      (footprint "MX-switch - switched pol")
      (description "Switch")
      (libsource (lib "Miscellaneous Devices") (part "SW-PB"))
    )
    (comp (ref "S296_1")
      (value "MX")
      (footprint "MX-switch")
      (description "Switch")
      (libsource (lib "Miscellaneous Devices") (part "SW-PB"))
    )
    (comp (ref "STAB1")
      (value "Plug")
      (footprint "Stab 2u")
      (libsource (lib "Miscellaneous Connectors") (part "Plug"))
    )
    (comp (ref "STAB2")
      (value "Plug")
      (footprint "Stab 2u")
      (libsource (lib "Miscellaneous Connectors") (part "Plug"))
    )
    (comp (ref "STAB3")
      (value "Plug")
      (footprint "Stab 2u")
      (libsource (lib "Miscellaneous Connectors") (part "Plug"))
    )
    (comp (ref "STAB4")
      (value "Plug")
      (footprint "Stab 2u")
      (libsource (lib "Miscellaneous Connectors") (part "Plug"))
    )
    (comp (ref "STAB5")
      (value "Plug")
      (footprint "Stab 2u")
      (libsource (lib "Miscellaneous Connectors") (part "Plug"))
    )
    (comp (ref "STAB6")
      (value "Plug")
      (footprint "Stab 6.25U")
      (libsource (lib "Miscellaneous Connectors") (part "Plug"))
    )
    (comp (ref "STAB8")
      (value "Plug")
      (footprint "Stab 2u")
      (libsource (lib "Miscellaneous Connectors") (part "Plug"))
    )
    (comp (ref "STAB9")
      (value "Plug")
      (footprint "Stab 3u")
      (libsource (lib "Miscellaneous Connectors") (part "Plug"))
    )
    (comp (ref "STAB10")
      (value "Plug")
      (footprint "Stab 3u")
      (libsource (lib "Miscellaneous Connectors") (part "Plug"))
    )
    (comp (ref "STAB11")
      (value "Plug")
      (footprint "Stab 2u")
      (libsource (lib "Miscellaneous Connectors") (part "Plug"))
    )
  )
  (nets
    (net (code "1") (name "/col1") (class "Default")
      (node (ref "S201") (pin "2") (pinfunction "2_2") (pintype "passive"))
      (node (ref "S217") (pin "2") (pinfunction "2_2") (pintype "passive"))
      (node (ref "S218") (pin "2") (pinfunction "2_2") (pintype "passive"))
      (node (ref "S234") (pin "2") (pinfunction "2_2") (pintype "passive"))
      (node (ref "S235") (pin "2") (pinfunction "2_2") (pintype "passive"))
      (node (ref "S251") (pin "2") (pinfunction "2_2") (pintype "passive"))
      (node (ref "S252") (pin "2") (pinfunction "2_2") (pintype "passive"))
      (node (ref "S265") (pin "2") (pinfunction "2_2") (pintype "passive"))
      (node (ref "S265_1") (pin "2") (pinfunction "2_2") (pintype "passive"))
      (node (ref "S266") (pin "2") (pinfunction "2_2") (pintype "passive"))
      (node (ref "S280") (pin "1") (pinfunction "1_1") (pintype "passive"))
      (node (ref "S290") (pin "2") (pinfunction "2_2") (pintype "passive"))
    )
    (net (code "2") (name "/col2") (class "Default")
      (node (ref "S202") (pin "2") (pinfunction "2_2") (pintype "passive"))
      (node (ref "S202_1") (pin "2") (pinfunction "2_2") (pintype "passive"))
      (node (ref "S203") (pin "2") (pinfunction "2_2") (pintype "passive"))
      (node (ref "S203_1") (pin "2") (pinfunction "2_2") (pintype "passive"))
      (node (ref "S219") (pin "2") (pinfunction "2_2") (pintype "passive"))
      (node (ref "S220") (pin "2") (pinfunction "2_2") (pintype "passive"))
      (node (ref "S236") (pin "2") (pinfunction "2_2") (pintype "passive"))
      (node (ref "S237") (pin "2") (pinfunction "2_2") (pintype "passive"))
      (node (ref "S253") (pin "2") (pinfunction "2_2") (pintype "passive"))
      (node (ref "S254") (pin "2") (pinfunction "2_2") (pintype "passive"))
      (node (ref "S267") (pin "2") (pinfunction "2_2") (pintype "passive"))
      (node (ref "S268") (pin "2") (pinfunction "2_2") (pintype "passive"))
      (node (ref "S281") (pin "1") (pinfunction "1_1") (pintype "passive"))
      (node (ref "S282") (pin "1") (pinfunction "1_1") (pintype "passive"))
    )
    (net (code "3") (name "/col3") (class "Default")
      (node (ref "S204") (pin "2") (pinfunction "2_2") (pintype "passive"))
      (node (ref "S204_1") (pin "2") (pinfunction "2_2") (pintype "passive"))
      (node (ref "S205") (pin "2") (pinfunction "2_2") (pintype "passive"))
      (node (ref "S205_1") (pin "2") (pinfunction "2_2") (pintype "passive"))
      (node (ref "S221") (pin "2") (pinfunction "2_2") (pintype "passive"))
      (node (ref "S222") (pin "2") (pinfunction "2_2") (pintype "passive"))
      (node (ref "S238") (pin "2") (pinfunction "2_2") (pintype "passive"))
      (node (ref "S239") (pin "2") (pinfunction "2_2") (pintype "passive"))
      (node (ref "S255") (pin "2") (pinfunction "2_2") (pintype "passive"))
      (node (ref "S256") (pin "2") (pinfunction "2_2") (pintype "passive"))
      (node (ref "S269") (pin "2") (pinfunction "2_2") (pintype "passive"))
      (node (ref "S270") (pin "2") (pinfunction "2_2") (pintype "passive"))
      (node (ref "S294") (pin "1") (pinfunction "1_1") (pintype "passive"))
      (node (ref "S294_2") (pin "2") (pinfunction "2_2") (pintype "passive"))
    )
    (net (code "4") (name "/col4") (class "Default")
      (node (ref "S206") (pin "2") (pinfunction "2_2") (pintype "passive"))
      (node (ref "S207") (pin "2") (pinfunction "2_2") (pintype "passive"))
      (node (ref "S223") (pin "2") (pinfunction "2_2") (pintype "passive"))
      (node (ref "S224") (pin "2") (pinfunction "2_2") (pintype "passive"))
      (node (ref "S240") (pin "2") (pinfunction "2_2") (pintype "passive"))
      (node (ref "S241") (pin "2") (pinfunction "2_2") (pintype "passive"))
      (node (ref "S257") (pin "2") (pinfunction "2_2") (pintype "passive"))
      (node (ref "S258") (pin "2") (pinfunction "2_2") (pintype "passive"))
      (node (ref "S271") (pin "2") (pinfunction "2_2") (pintype "passive"))
      (node (ref "S272") (pin "2") (pinfunction "2_2") (pintype "passive"))
      (node (ref "S283") (pin "2") (pinfunction "2_2") (pintype "passive"))
      (node (ref "S283_1") (pin "2") (pinfunction "2_2") (pintype "passive"))
      (node (ref "S283_2") (pin "2") (pinfunction "2_2") (pintype "passive"))
      (node (ref "S295") (pin "1") (pinfunction "1_1") (pintype "passive"))
      (node (ref "S295_2") (pin "2") (pinfunction "2_2") (pintype "passive"))
    )
    (net (code "5") (name "/col5") (class "Default")
      (node (ref "S208") (pin "2") (pinfunction "2_2") (pintype "passive"))
      (node (ref "S209") (pin "2") (pinfunction "2_2") (pintype "passive"))
      (node (ref "S209_1") (pin "2") (pinfunction "2_2") (pintype "passive"))
      (node (ref "S225") (pin "2") (pinfunction "2_2") (pintype "passive"))
      (node (ref "S226") (pin "2") (pinfunction "2_2") (pintype "passive"))
      (node (ref "S242") (pin "2") (pinfunction "2_2") (pintype "passive"))
      (node (ref "S243") (pin "2") (pinfunction "2_2") (pintype "passive"))
      (node (ref "S259") (pin "2") (pinfunction "2_2") (pintype "passive"))
      (node (ref "S260") (pin "2") (pinfunction "2_2") (pintype "passive"))
      (node (ref "S273") (pin "2") (pinfunction "2_2") (pintype "passive"))
      (node (ref "S274") (pin "2") (pinfunction "2_2") (pintype "passive"))
      (node (ref "S284") (pin "2") (pinfunction "2_2") (pintype "passive"))
      (node (ref "S293") (pin "2") (pinfunction "2_2") (pintype "passive"))
    )
    (net (code "6") (name "/col6") (class "Default")
      (node (ref "S210") (pin "2") (pinfunction "2_2") (pintype "passive"))
      (node (ref "S210_1") (pin "2") (pinfunction "2_2") (pintype "passive"))
      (node (ref "S211") (pin "2") (pinfunction "2_2") (pintype "passive"))
      (node (ref "S211_1") (pin "2") (pinfunction "2_2") (pintype "passive"))
      (node (ref "S227") (pin "2") (pinfunction "2_2") (pintype "passive"))
      (node (ref "S228") (pin "2") (pinfunction "2_2") (pintype "passive"))
      (node (ref "S244") (pin "2") (pinfunction "2_2") (pintype "passive"))
      (node (ref "S245") (pin "2") (pinfunction "2_2") (pintype "passive"))
      (node (ref "S261") (pin "2") (pinfunction "2_2") (pintype "passive"))
      (node (ref "S262") (pin "2") (pinfunction "2_2") (pintype "passive"))
      (node (ref "S275") (pin "2") (pinfunction "2_2") (pintype "passive"))
      (node (ref "S276") (pin "2") (pinfunction "2_2") (pintype "passive"))
      (node (ref "S285") (pin "2") (pinfunction "2_2") (pintype "passive"))
      (node (ref "S286") (pin "2") (pinfunction "2_2") (pintype "passive"))
    )
    (net (code "7") (name "/col7") (class "Default")
      (node (ref "S212") (pin "2") (pinfunction "2_2") (pintype "passive"))
      (node (ref "S212_1") (pin "2") (pinfunction "2_2") (pintype "passive"))
      (node (ref "S213") (pin "2") (pinfunction "2_2") (pintype "passive"))
      (node (ref "S229") (pin "2") (pinfunction "2_2") (pintype "passive"))
      (node (ref "S230") (pin "2") (pinfunction "2_2") (pintype "passive"))
      (node (ref "S246") (pin "2") (pinfunction "2_2") (pintype "passive"))
      (node (ref "S247") (pin "2") (pinfunction "2_2") (pintype "passive"))
      (node (ref "S263") (pin "2") (pinfunction "2_2") (pintype "passive"))
      (node (ref "S277") (pin "2") (pinfunction "2_2") (pintype "passive"))
      (node (ref "S277_1") (pin "2") (pinfunction "2_2") (pintype "passive"))
      (node (ref "S278") (pin "2") (pinfunction "2_2") (pintype "passive"))
      (node (ref "S287") (pin "2") (pinfunction "2_2") (pintype "passive"))
      (node (ref "S288") (pin "2") (pinfunction "2_2") (pintype "passive"))
      (node (ref "S296") (pin "2") (pinfunction "2_2") (pintype "passive"))
      (node (ref "S296_1") (pin "2") (pinfunction "2_2") (pintype "passive"))
    )
    (net (code "8") (name "/col8") (class "Default")
      (node (ref "S214") (pin "2") (pinfunction "2_2") (pintype "passive"))
      (node (ref "S215") (pin "2") (pinfunction "2_2") (pintype "passive"))
      (node (ref "S216") (pin "2") (pinfunction "2_2") (pintype "passive"))
      (node (ref "S231") (pin "2") (pinfunction "2_2") (pintype "passive"))
      (node (ref "S232") (pin "2") (pinfunction "2_2") (pintype "passive"))
      (node (ref "S233") (pin "2") (pinfunction "2_2") (pintype "passive"))
      (node (ref "S248") (pin "2") (pinfunction "2_2") (pintype "passive"))
      (node (ref "S249") (pin "2") (pinfunction "2_2") (pintype "passive"))
      (node (ref "S250") (pin "2") (pinfunction "2_2") (pintype "passive"))
      (node (ref "S264") (pin "1") (pinfunction "1_1") (pintype "passive"))
      (node (ref "S264_1") (pin "1") (pinfunction "1_1") (pintype "passive"))
      (node (ref "S279") (pin "2") (pinfunction "2_2") (pintype "passive"))
      (node (ref "S289") (pin "2") (pinfunction "2_2") (pintype "passive"))
    )
    (net (code "9") (name "/row1") (class "Default")
      (node (ref "D201") (pin "2") (pinfunction "K_2") (pintype "passive"))
      (node (ref "D202") (pin "2") (pinfunction "K_2") (pintype "passive"))
      (node (ref "D204") (pin "2") (pinfunction "K_2") (pintype "passive"))
      (node (ref "D206") (pin "2") (pinfunction "K_2") (pintype "passive"))
      (node (ref "D208") (pin "2") (pinfunction "K_2") (pintype "passive"))
      (node (ref "D210") (pin "2") (pinfunction "K_2") (pintype "passive"))
      (node (ref "D212") (pin "2") (pinfunction "K_2") (pintype "passive"))
      (node (ref "D214") (pin "2") (pinfunction "K_2") (pintype "passive"))
    )
    (net (code "10") (name "/row2") (class "Default")
      (node (ref "D203") (pin "2") (pinfunction "K_2") (pintype "passive"))
      (node (ref "D205") (pin "2") (pinfunction "K_2") (pintype "passive"))
      (node (ref "D207") (pin "2") (pinfunction "K_2") (pintype "passive"))
      (node (ref "D209") (pin "2") (pinfunction "K_2") (pintype "passive"))
      (node (ref "D211") (pin "2") (pinfunction "K_2") (pintype "passive"))
      (node (ref "D213") (pin "2") (pinfunction "K_2") (pintype "passive"))
      (node (ref "D215") (pin "2") (pinfunction "K_2") (pintype "passive"))
      (node (ref "D290") (pin "2") (pinfunction "K_2") (pintype "passive"))
    )
    (net (code "11") (name "/row3") (class "Default")
      (node (ref "D217") (pin "2") (pinfunction "K_2") (pintype "passive"))
      (node (ref "D219") (pin "2") (pinfunction "K_2") (pintype "passive"))
      (node (ref "D221") (pin "2") (pinfunction "K_2") (pintype "passive"))
      (node (ref "D223") (pin "2") (pinfunction "K_2") (pintype "passive"))
      (node (ref "D225") (pin "2") (pinfunction "K_2") (pintype "passive"))
      (node (ref "D227") (pin "2") (pinfunction "K_2") (pintype "passive"))
      (node (ref "D229") (pin "2") (pinfunction "K_2") (pintype "passive"))
      (node (ref "D231") (pin "2") (pinfunction "K_2") (pintype "passive"))
    )
    (net (code "12") (name "/row4") (class "Default")
      (node (ref "D216") (pin "2") (pinfunction "K_2") (pintype "passive"))
      (node (ref "D218") (pin "2") (pinfunction "K_2") (pintype "passive"))
      (node (ref "D220") (pin "2") (pinfunction "K_2") (pintype "passive"))
      (node (ref "D222") (pin "2") (pinfunction "K_2") (pintype "passive"))
      (node (ref "D224") (pin "2") (pinfunction "K_2") (pintype "passive"))
      (node (ref "D226") (pin "2") (pinfunction "K_2") (pintype "passive"))
      (node (ref "D228") (pin "2") (pinfunction "K_2") (pintype "passive"))
      (node (ref "D230") (pin "2") (pinfunction "K_2") (pintype "passive"))
    )
    (net (code "13") (name "/row5") (class "Default")
      (node (ref "D234") (pin "2") (pinfunction "K_2") (pintype "passive"))
      (node (ref "D236") (pin "2") (pinfunction "K_2") (pintype "passive"))
      (node (ref "D238") (pin "2") (pinfunction "K_2") (pintype "passive"))
      (node (ref "D240") (pin "2") (pinfunction "K_2") (pintype "passive"))
      (node (ref "D242") (pin "2") (pinfunction "K_2") (pintype "passive"))
      (node (ref "D244") (pin "2") (pinfunction "K_2") (pintype "passive"))
      (node (ref "D246") (pin "2") (pinfunction "K_2") (pintype "passive"))
      (node (ref "D248") (pin "2") (pinfunction "K_2") (pintype "passive"))
    )
    (net (code "14") (name "/row6") (class "Default")
      (node (ref "D232") (pin "2") (pinfunction "K_2") (pintype "passive"))
      (node (ref "D235") (pin "2") (pinfunction "K_2") (pintype "passive"))
      (node (ref "D237") (pin "2") (pinfunction "K_2") (pintype "passive"))
      (node (ref "D239") (pin "2") (pinfunction "K_2") (pintype "passive"))
      (node (ref "D241") (pin "2") (pinfunction "K_2") (pintype "passive"))
      (node (ref "D243") (pin "2") (pinfunction "K_2") (pintype "passive"))
      (node (ref "D245") (pin "2") (pinfunction "K_2") (pintype "passive"))
      (node (ref "D247") (pin "2") (pinfunction "K_2") (pintype "passive"))
    )
    (net (code "15") (name "/row7") (class "Default")
      (node (ref "D251") (pin "2") (pinfunction "K_2") (pintype "passive"))
      (node (ref "D253") (pin "2") (pinfunction "K_2") (pintype "passive"))
      (node (ref "D255") (pin "2") (pinfunction "K_2") (pintype "passive"))
      (node (ref "D257") (pin "2") (pinfunction "K_2") (pintype "passive"))
      (node (ref "D259") (pin "2") (pinfunction "K_2") (pintype "passive"))
      (node (ref "D261") (pin "2") (pinfunction "K_2") (pintype "passive"))
      (node (ref "D263") (pin "2") (pinfunction "K_2") (pintype "passive"))
      (node (ref "D264") (pin "2") (pinfunction "K_2") (pintype "passive"))
    )
    (net (code "16") (name "/row8") (class "Default")
      (node (ref "D249") (pin "2") (pinfunction "K_2") (pintype "passive"))
      (node (ref "D252") (pin "2") (pinfunction "K_2") (pintype "passive"))
      (node (ref "D254") (pin "2") (pinfunction "K_2") (pintype "passive"))
      (node (ref "D256") (pin "2") (pinfunction "K_2") (pintype "passive"))
      (node (ref "D258") (pin "2") (pinfunction "K_2") (pintype "passive"))
      (node (ref "D260") (pin "2") (pinfunction "K_2") (pintype "passive"))
      (node (ref "D262") (pin "2") (pinfunction "K_2") (pintype "passive"))
      (node (ref "D296") (pin "2") (pinfunction "K_2") (pintype "passive"))
    )
    (net (code "17") (name "/row9") (class "Default")
      (node (ref "D265") (pin "2") (pinfunction "K_2") (pintype "passive"))
      (node (ref "D267") (pin "2") (pinfunction "K_2") (pintype "passive"))
      (node (ref "D269") (pin "2") (pinfunction "K_2") (pintype "passive"))
      (node (ref "D271") (pin "2") (pinfunction "K_2") (pintype "passive"))
      (node (ref "D273") (pin "2") (pinfunction "K_2") (pintype "passive"))
      (node (ref "D275") (pin "2") (pinfunction "K_2") (pintype "passive"))
      (node (ref "D277") (pin "2") (pinfunction "K_2") (pintype "passive"))
      (node (ref "D279") (pin "2") (pinfunction "K_2") (pintype "passive"))
    )
    (net (code "18") (name "/row10") (class "Default")
      (node (ref "D233") (pin "2") (pinfunction "K_2") (pintype "passive"))
      (node (ref "D266") (pin "2") (pinfunction "K_2") (pintype "passive"))
      (node (ref "D268") (pin "2") (pinfunction "K_2") (pintype "passive"))
      (node (ref "D270") (pin "2") (pinfunction "K_2") (pintype "passive"))
      (node (ref "D272") (pin "2") (pinfunction "K_2") (pintype "passive"))
      (node (ref "D274") (pin "2") (pinfunction "K_2") (pintype "passive"))
      (node (ref "D276") (pin "2") (pinfunction "K_2") (pintype "passive"))
      (node (ref "D278") (pin "2") (pinfunction "K_2") (pintype "passive"))
    )
    (net (code "19") (name "/row11") (class "Default")
      (node (ref "D280") (pin "2") (pinfunction "K_2") (pintype "passive"))
      (node (ref "D282") (pin "2") (pinfunction "K_2") (pintype "passive"))
      (node (ref "D283") (pin "2") (pinfunction "K_2") (pintype "passive"))
      (node (ref "D285") (pin "2") (pinfunction "K_2") (pintype "passive"))
      (node (ref "D287") (pin "2") (pinfunction "K_2") (pintype "passive"))
      (node (ref "D289") (pin "2") (pinfunction "K_2") (pintype "passive"))
      (node (ref "D293") (pin "2") (pinfunction "K_2") (pintype "passive"))
    )
    (net (code "20") (name "/row12") (class "Default")
      (node (ref "D250") (pin "2") (pinfunction "K_2") (pintype "passive"))
      (node (ref "D281") (pin "2") (pinfunction "K_2") (pintype "passive"))
      (node (ref "D284") (pin "2") (pinfunction "K_2") (pintype "passive"))
      (node (ref "D286") (pin "2") (pinfunction "K_2") (pintype "passive"))
      (node (ref "D288") (pin "2") (pinfunction "K_2") (pintype "passive"))
      (node (ref "D294") (pin "2") (pinfunction "K_2") (pintype "passive"))
      (node (ref "D295") (pin "2") (pinfunction "K_2") (pintype "passive"))
    )
    (net (code "21") (name "Net-(D201-A)") (class "Default")
      (node (ref "D201") (pin "1") (pinfunction "A_1") (pintype "passive"))
      (node (ref "S201") (pin "1") (pinfunction "1_1") (pintype "passive"))
    )
    (net (code "22") (name "Net-(D202-A)") (class "Default")
      (node (ref "D202") (pin "1") (pinfunction "A_1") (pintype "passive"))
      (node (ref "S202") (pin "1") (pinfunction "1_1") (pintype "passive"))
      (node (ref "S202_1") (pin "1") (pinfunction "1_1") (pintype "passive"))
    )
    (net (code "23") (name "Net-(D203-A)") (class "Default")
      (node (ref "D203") (pin "1") (pinfunction "A_1") (pintype "passive"))
      (node (ref "S203") (pin "1") (pinfunction "1_1") (pintype "passive"))
      (node (ref "S203_1") (pin "1") (pinfunction "1_1") (pintype "passive"))
    )
    (net (code "24") (name "Net-(D204-A)") (class "Default")
      (node (ref "D204") (pin "1") (pinfunction "A_1") (pintype "passive"))
      (node (ref "S204") (pin "1") (pinfunction "1_1") (pintype "passive"))
      (node (ref "S204_1") (pin "1") (pinfunction "1_1") (pintype "passive"))
    )
    (net (code "25") (name "Net-(D205-A)") (class "Default")
      (node (ref "D205") (pin "1") (pinfunction "A_1") (pintype "passive"))
      (node (ref "S205") (pin "1") (pinfunction "1_1") (pintype "passive"))
      (node (ref "S205_1") (pin "1") (pinfunction "1_1") (pintype "passive"))
    )
    (net (code "26") (name "Net-(D206-A)") (class "Default")
      (node (ref "D206") (pin "1") (pinfunction "A_1") (pintype "passive"))
      (node (ref "S206") (pin "1") (pinfunction "1_1") (pintype "passive"))
    )
    (net (code "27") (name "Net-(D207-A)") (class "Default")
      (node (ref "D207") (pin "1") (pinfunction "A_1") (pintype "passive"))
      (node (ref "S207") (pin "1") (pinfunction "1_1") (pintype "passive"))
    )
    (net (code "28") (name "Net-(D208-A)") (class "Default")
      (node (ref "D208") (pin "1") (pinfunction "A_1") (pintype "passive"))
      (node (ref "S208") (pin "1") (pinfunction "1_1") (pintype "passive"))
    )
    (net (code "29") (name "Net-(D209-A)") (class "Default")
      (node (ref "D209") (pin "1") (pinfunction "A_1") (pintype "passive"))
      (node (ref "S209") (pin "1") (pinfunction "1_1") (pintype "passive"))
      (node (ref "S209_1") (pin "1") (pinfunction "1_1") (pintype "passive"))
    )
    (net (code "30") (name "Net-(D210-A)") (class "Default")
      (node (ref "D210") (pin "1") (pinfunction "A_1") (pintype "passive"))
      (node (ref "S210") (pin "1") (pinfunction "1_1") (pintype "passive"))
      (node (ref "S210_1") (pin "1") (pinfunction "1_1") (pintype "passive"))
    )
    (net (code "31") (name "Net-(D211-A)") (class "Default")
      (node (ref "D211") (pin "1") (pinfunction "A_1") (pintype "passive"))
      (node (ref "S211") (pin "1") (pinfunction "1_1") (pintype "passive"))
      (node (ref "S211_1") (pin "1") (pinfunction "1_1") (pintype "passive"))
    )
    (net (code "32") (name "Net-(D212-A)") (class "Default")
      (node (ref "D212") (pin "1") (pinfunction "A_1") (pintype "passive"))
      (node (ref "S212") (pin "1") (pinfunction "1_1") (pintype "passive"))
      (node (ref "S212_1") (pin "1") (pinfunction "1_1") (pintype "passive"))
    )
    (net (code "33") (name "Net-(D213-A)") (class "Default")
      (node (ref "D213") (pin "1") (pinfunction "A_1") (pintype "passive"))
      (node (ref "S213") (pin "1") (pinfunction "1_1") (pintype "passive"))
    )
    (net (code "34") (name "Net-(D214-A)") (class "Default")
      (node (ref "D214") (pin "1") (pinfunction "A_1") (pintype "passive"))
      (node (ref "S214") (pin "1") (pinfunction "1_1") (pintype "passive"))
    )
    (net (code "35") (name "Net-(D215-A)") (class "Default")
      (node (ref "D215") (pin "1") (pinfunction "A_1") (pintype "passive"))
      (node (ref "S215") (pin "1") (pinfunction "1_1") (pintype "passive"))
    )
    (net (code "36") (name "Net-(D216-A)") (class "Default")
      (node (ref "D216") (pin "1") (pinfunction "A_1") (pintype "passive"))
      (node (ref "S216") (pin "1") (pinfunction "1_1") (pintype "passive"))
    )
    (net (code "37") (name "Net-(D217-A)") (class "Default")
      (node (ref "D217") (pin "1") (pinfunction "A_1") (pintype "passive"))
      (node (ref "S217") (pin "1") (pinfunction "1_1") (pintype "passive"))
    )
    (net (code "38") (name "Net-(D218-A)") (class "Default")
      (node (ref "D218") (pin "1") (pinfunction "A_1") (pintype "passive"))
      (node (ref "S218") (pin "1") (pinfunction "1_1") (pintype "passive"))
    )
    (net (code "39") (name "Net-(D219-A)") (class "Default")
      (node (ref "D219") (pin "1") (pinfunction "A_1") (pintype "passive"))
      (node (ref "S219") (pin "1") (pinfunction "1_1") (pintype "passive"))
    )
    (net (code "40") (name "Net-(D220-A)") (class "Default")
      (node (ref "D220") (pin "1") (pinfunction "A_1") (pintype "passive"))
      (node (ref "S220") (pin "1") (pinfunction "1_1") (pintype "passive"))
    )
    (net (code "41") (name "Net-(D221-A)") (class "Default")
      (node (ref "D221") (pin "1") (pinfunction "A_1") (pintype "passive"))
      (node (ref "S221") (pin "1") (pinfunction "1_1") (pintype "passive"))
    )
    (net (code "42") (name "Net-(D222-A)") (class "Default")
      (node (ref "D222") (pin "1") (pinfunction "A_1") (pintype "passive"))
      (node (ref "S222") (pin "1") (pinfunction "1_1") (pintype "passive"))
    )
    (net (code "43") (name "Net-(D223-A)") (class "Default")
      (node (ref "D223") (pin "1") (pinfunction "A_1") (pintype "passive"))
      (node (ref "S223") (pin "1") (pinfunction "1_1") (pintype "passive"))
    )
    (net (code "44") (name "Net-(D224-A)") (class "Default")
      (node (ref "D224") (pin "1") (pinfunction "A_1") (pintype "passive"))
      (node (ref "S224") (pin "1") (pinfunction "1_1") (pintype "passive"))
    )
    (net (code "45") (name "Net-(D225-A)") (class "Default")
      (node (ref "D225") (pin "1") (pinfunction "A_1") (pintype "passive"))
      (node (ref "S225") (pin "1") (pinfunction "1_1") (pintype "passive"))
    )
    (net (code "46") (name "Net-(D226-A)") (class "Default")
      (node (ref "D226") (pin "1") (pinfunction "A_1") (pintype "passive"))
      (node (ref "S226") (pin "1") (pinfunction "1_1") (pintype "passive"))
    )
    (net (code "47") (name "Net-(D227-A)") (class "Default")
      (node (ref "D227") (pin "1") (pinfunction "A_1") (pintype "passive"))
      (node (ref "S227") (pin "1") (pinfunction "1_1") (pintype "passive"))
    )
    (net (code "48") (name "Net-(D228-A)") (class "Default")
      (node (ref "D228") (pin "1") (pinfunction "A_1") (pintype "passive"))
      (node (ref "S228") (pin "1") (pinfunction "1_1") (pintype "passive"))
    )
    (net (code "49") (name "Net-(D229-A)") (class "Default")
      (node (ref "D229") (pin "1") (pinfunction "A_1") (pintype "passive"))
      (node (ref "S229") (pin "1") (pinfunction "1_1") (pintype "passive"))
    )
    (net (code "50") (name "Net-(D230-A)") (class "Default")
      (node (ref "D230") (pin "1") (pinfunction "A_1") (pintype "passive"))
      (node (ref "S230") (pin "1") (pinfunction "1_1") (pintype "passive"))
    )
    (net (code "51") (name "Net-(D231-A)") (class "Default")
      (node (ref "D231") (pin "1") (pinfunction "A_1") (pintype "passive"))
      (node (ref "S231") (pin "1") (pinfunction "1_1") (pintype "passive"))
    )
    (net (code "52") (name "Net-(D232-A)") (class "Default")
      (node (ref "D232") (pin "1") (pinfunction "A_1") (pintype "passive"))
      (node (ref "S232") (pin "1") (pinfunction "1_1") (pintype "passive"))
    )
    (net (code "53") (name "Net-(D233-A)") (class "Default")
      (node (ref "D233") (pin "1") (pinfunction "A_1") (pintype "passive"))
      (node (ref "S233") (pin "1") (pinfunction "1_1") (pintype "passive"))
    )
    (net (code "54") (name "Net-(D234-A)") (class "Default")
      (node (ref "D234") (pin "1") (pinfunction "A_1") (pintype "passive"))
      (node (ref "S234") (pin "1") (pinfunction "1_1") (pintype "passive"))
    )
    (net (code "55") (name "Net-(D235-A)") (class "Default")
      (node (ref "D235") (pin "1") (pinfunction "A_1") (pintype "passive"))
      (node (ref "S235") (pin "1") (pinfunction "1_1") (pintype "passive"))
    )
    (net (code "56") (name "Net-(D236-A)") (class "Default")
      (node (ref "D236") (pin "1") (pinfunction "A_1") (pintype "passive"))
      (node (ref "S236") (pin "1") (pinfunction "1_1") (pintype "passive"))
    )
    (net (code "57") (name "Net-(D237-A)") (class "Default")
      (node (ref "D237") (pin "1") (pinfunction "A_1") (pintype "passive"))
      (node (ref "S237") (pin "1") (pinfunction "1_1") (pintype "passive"))
    )
    (net (code "58") (name "Net-(D238-A)") (class "Default")
      (node (ref "D238") (pin "1") (pinfunction "A_1") (pintype "passive"))
      (node (ref "S238") (pin "1") (pinfunction "1_1") (pintype "passive"))
    )
    (net (code "59") (name "Net-(D239-A)") (class "Default")
      (node (ref "D239") (pin "1") (pinfunction "A_1") (pintype "passive"))
      (node (ref "S239") (pin "1") (pinfunction "1_1") (pintype "passive"))
    )
    (net (code "60") (name "Net-(D240-A)") (class "Default")
      (node (ref "D240") (pin "1") (pinfunction "A_1") (pintype "passive"))
      (node (ref "S240") (pin "1") (pinfunction "1_1") (pintype "passive"))
    )
    (net (code "61") (name "Net-(D241-A)") (class "Default")
      (node (ref "D241") (pin "1") (pinfunction "A_1") (pintype "passive"))
      (node (ref "S241") (pin "1") (pinfunction "1_1") (pintype "passive"))
    )
    (net (code "62") (name "Net-(D242-A)") (class "Default")
      (node (ref "D242") (pin "1") (pinfunction "A_1") (pintype "passive"))
      (node (ref "S242") (pin "1") (pinfunction "1_1") (pintype "passive"))
    )
    (net (code "63") (name "Net-(D243-A)") (class "Default")
      (node (ref "D243") (pin "1") (pinfunction "A_1") (pintype "passive"))
      (node (ref "S243") (pin "1") (pinfunction "1_1") (pintype "passive"))
    )
    (net (code "64") (name "Net-(D244-A)") (class "Default")
      (node (ref "D244") (pin "1") (pinfunction "A_1") (pintype "passive"))
      (node (ref "S244") (pin "1") (pinfunction "1_1") (pintype "passive"))
    )
    (net (code "65") (name "Net-(D245-A)") (class "Default")
      (node (ref "D245") (pin "1") (pinfunction "A_1") (pintype "passive"))
      (node (ref "S245") (pin "1") (pinfunction "1_1") (pintype "passive"))
    )
    (net (code "66") (name "Net-(D246-A)") (class "Default")
      (node (ref "D246") (pin "1") (pinfunction "A_1") (pintype "passive"))
      (node (ref "S246") (pin "1") (pinfunction "1_1") (pintype "passive"))
    )
    (net (code "67") (name "Net-(D247-A)") (class "Default")
      (node (ref "D247") (pin "1") (pinfunction "A_1") (pintype "passive"))
      (node (ref "S247") (pin "1") (pinfunction "1_1") (pintype "passive"))
    )
    (net (code "68") (name "Net-(D248-A)") (class "Default")
      (node (ref "D248") (pin "1") (pinfunction "A_1") (pintype "passive"))
      (node (ref "S248") (pin "1") (pinfunction "1_1") (pintype "passive"))
    )
    (net (code "69") (name "Net-(D249-A)") (class "Default")
      (node (ref "D249") (pin "1") (pinfunction "A_1") (pintype "passive"))
      (node (ref "S249") (pin "1") (pinfunction "1_1") (pintype "passive"))
    )
    (net (code "70") (name "Net-(D250-A)") (class "Default")
      (node (ref "D250") (pin "1") (pinfunction "A_1") (pintype "passive"))
      (node (ref "S250") (pin "1") (pinfunction "1_1") (pintype "passive"))
    )
    (net (code "71") (name "Net-(D251-A)") (class "Default")
      (node (ref "D251") (pin "1") (pinfunction "A_1") (pintype "passive"))
      (node (ref "S251") (pin "1") (pinfunction "1_1") (pintype "passive"))
    )
    (net (code "72") (name "Net-(D252-A)") (class "Default")
      (node (ref "D252") (pin "1") (pinfunction "A_1") (pintype "passive"))
      (node (ref "S252") (pin "1") (pinfunction "1_1") (pintype "passive"))
    )
    (net (code "73") (name "Net-(D253-A)") (class "Default")
      (node (ref "D253") (pin "1") (pinfunction "A_1") (pintype "passive"))
      (node (ref "S253") (pin "1") (pinfunction "1_1") (pintype "passive"))
    )
    (net (code "74") (name "Net-(D254-A)") (class "Default")
      (node (ref "D254") (pin "1") (pinfunction "A_1") (pintype "passive"))
      (node (ref "S254") (pin "1") (pinfunction "1_1") (pintype "passive"))
    )
    (net (code "75") (name "Net-(D255-A)") (class "Default")
      (node (ref "D255") (pin "1") (pinfunction "A_1") (pintype "passive"))
      (node (ref "S255") (pin "1") (pinfunction "1_1") (pintype "passive"))
    )
    (net (code "76") (name "Net-(D256-A)") (class "Default")
      (node (ref "D256") (pin "1") (pinfunction "A_1") (pintype "passive"))
      (node (ref "S256") (pin "1") (pinfunction "1_1") (pintype "passive"))
    )
    (net (code "77") (name "Net-(D257-A)") (class "Default")
      (node (ref "D257") (pin "1") (pinfunction "A_1") (pintype "passive"))
      (node (ref "S257") (pin "1") (pinfunction "1_1") (pintype "passive"))
    )
    (net (code "78") (name "Net-(D258-A)") (class "Default")
      (node (ref "D258") (pin "1") (pinfunction "A_1") (pintype "passive"))
      (node (ref "S258") (pin "1") (pinfunction "1_1") (pintype "passive"))
    )
    (net (code "79") (name "Net-(D259-A)") (class "Default")
      (node (ref "D259") (pin "1") (pinfunction "A_1") (pintype "passive"))
      (node (ref "S259") (pin "1") (pinfunction "1_1") (pintype "passive"))
    )
    (net (code "80") (name "Net-(D260-A)") (class "Default")
      (node (ref "D260") (pin "1") (pinfunction "A_1") (pintype "passive"))
      (node (ref "S260") (pin "1") (pinfunction "1_1") (pintype "passive"))
    )
    (net (code "81") (name "Net-(D261-A)") (class "Default")
      (node (ref "D261") (pin "1") (pinfunction "A_1") (pintype "passive"))
      (node (ref "S261") (pin "1") (pinfunction "1_1") (pintype "passive"))
    )
    (net (code "82") (name "Net-(D262-A)") (class "Default")
      (node (ref "D262") (pin "1") (pinfunction "A_1") (pintype "passive"))
      (node (ref "S262") (pin "1") (pinfunction "1_1") (pintype "passive"))
    )
    (net (code "83") (name "Net-(D263-A)") (class "Default")
      (node (ref "D263") (pin "1") (pinfunction "A_1") (pintype "passive"))
      (node (ref "S263") (pin "1") (pinfunction "1_1") (pintype "passive"))
    )
    (net (code "84") (name "Net-(D264-A)") (class "Default")
      (node (ref "D264") (pin "1") (pinfunction "A_1") (pintype "passive"))
      (node (ref "S264") (pin "2") (pinfunction "2_2") (pintype "passive"))
      (node (ref "S264_1") (pin "2") (pinfunction "2_2") (pintype "passive"))
    )
    (net (code "85") (name "Net-(D265-A)") (class "Default")
      (node (ref "D265") (pin "1") (pinfunction "A_1") (pintype "passive"))
      (node (ref "S265") (pin "1") (pinfunction "1_1") (pintype "passive"))
      (node (ref "S265_1") (pin "1") (pinfunction "1_1") (pintype "passive"))
    )
    (net (code "86") (name "Net-(D266-A)") (class "Default")
      (node (ref "D266") (pin "1") (pinfunction "A_1") (pintype "passive"))
      (node (ref "S266") (pin "1") (pinfunction "1_1") (pintype "passive"))
    )
    (net (code "87") (name "Net-(D267-A)") (class "Default")
      (node (ref "D267") (pin "1") (pinfunction "A_1") (pintype "passive"))
      (node (ref "S267") (pin "1") (pinfunction "1_1") (pintype "passive"))
    )
    (net (code "88") (name "Net-(D268-A)") (class "Default")
      (node (ref "D268") (pin "1") (pinfunction "A_1") (pintype "passive"))
      (node (ref "S268") (pin "1") (pinfunction "1_1") (pintype "passive"))
    )
    (net (code "89") (name "Net-(D269-A)") (class "Default")
      (node (ref "D269") (pin "1") (pinfunction "A_1") (pintype "passive"))
      (node (ref "S269") (pin "1") (pinfunction "1_1") (pintype "passive"))
    )
    (net (code "90") (name "Net-(D270-A)") (class "Default")
      (node (ref "D270") (pin "1") (pinfunction "A_1") (pintype "passive"))
      (node (ref "S270") (pin "1") (pinfunction "1_1") (pintype "passive"))
    )
    (net (code "91") (name "Net-(D271-A)") (class "Default")
      (node (ref "D271") (pin "1") (pinfunction "A_1") (pintype "passive"))
      (node (ref "S271") (pin "1") (pinfunction "1_1") (pintype "passive"))
    )
    (net (code "92") (name "Net-(D272-A)") (class "Default")
      (node (ref "D272") (pin "1") (pinfunction "A_1") (pintype "passive"))
      (node (ref "S272") (pin "1") (pinfunction "1_1") (pintype "passive"))
    )
    (net (code "93") (name "Net-(D273-A)") (class "Default")
      (node (ref "D273") (pin "1") (pinfunction "A_1") (pintype "passive"))
      (node (ref "S273") (pin "1") (pinfunction "1_1") (pintype "passive"))
    )
    (net (code "94") (name "Net-(D274-A)") (class "Default")
      (node (ref "D274") (pin "1") (pinfunction "A_1") (pintype "passive"))
      (node (ref "S274") (pin "1") (pinfunction "1_1") (pintype "passive"))
    )
    (net (code "95") (name "Net-(D275-A)") (class "Default")
      (node (ref "D275") (pin "1") (pinfunction "A_1") (pintype "passive"))
      (node (ref "S275") (pin "1") (pinfunction "1_1") (pintype "passive"))
    )
    (net (code "96") (name "Net-(D276-A)") (class "Default")
      (node (ref "D276") (pin "1") (pinfunction "A_1") (pintype "passive"))
      (node (ref "S276") (pin "1") (pinfunction "1_1") (pintype "passive"))
    )
    (net (code "97") (name "Net-(D277-A)") (class "Default")
      (node (ref "D277") (pin "1") (pinfunction "A_1") (pintype "passive"))
      (node (ref "S277") (pin "1") (pinfunction "1_1") (pintype "passive"))
      (node (ref "S277_1") (pin "1") (pinfunction "1_1") (pintype "passive"))
    )
    (net (code "98") (name "Net-(D278-A)") (class "Default")
      (node (ref "D278") (pin "1") (pinfunction "A_1") (pintype "passive"))
      (node (ref "S278") (pin "1") (pinfunction "1_1") (pintype "passive"))
    )
    (net (code "99") (name "Net-(D279-A)") (class "Default")
      (node (ref "D279") (pin "1") (pinfunction "A_1") (pintype "passive"))
      (node (ref "S279") (pin "1") (pinfunction "1_1") (pintype "passive"))
    )
    (net (code "100") (name "Net-(D280-A)") (class "Default")
      (node (ref "D280") (pin "1") (pinfunction "A_1") (pintype "passive"))
      (node (ref "S280") (pin "2") (pinfunction "2_2") (pintype "passive"))
    )
    (net (code "101") (name "Net-(D281-A)") (class "Default")
      (node (ref "D281") (pin "1") (pinfunction "A_1") (pintype "passive"))
      (node (ref "S281") (pin "2") (pinfunction "2_2") (pintype "passive"))
    )
    (net (code "102") (name "Net-(D282-A)") (class "Default")
      (node (ref "D282") (pin "1") (pinfunction "A_1") (pintype "passive"))
      (node (ref "S282") (pin "2") (pinfunction "2_2") (pintype "passive"))
    )
    (net (code "103") (name "Net-(D283-A)") (class "Default")
      (node (ref "D283") (pin "1") (pinfunction "A_1") (pintype "passive"))
      (node (ref "S283") (pin "1") (pinfunction "1_1") (pintype "passive"))
      (node (ref "S283_1") (pin "1") (pinfunction "1_1") (pintype "passive"))
      (node (ref "S283_2") (pin "1") (pinfunction "1_1") (pintype "passive"))
    )
    (net (code "104") (name "Net-(D284-A)") (class "Default")
      (node (ref "D284") (pin "1") (pinfunction "A_1") (pintype "passive"))
      (node (ref "S284") (pin "1") (pinfunction "1_1") (pintype "passive"))
    )
    (net (code "105") (name "Net-(D285-A)") (class "Default")
      (node (ref "D285") (pin "1") (pinfunction "A_1") (pintype "passive"))
      (node (ref "S285") (pin "1") (pinfunction "1_1") (pintype "passive"))
    )
    (net (code "106") (name "Net-(D286-A)") (class "Default")
      (node (ref "D286") (pin "1") (pinfunction "A_1") (pintype "passive"))
      (node (ref "S286") (pin "1") (pinfunction "1_1") (pintype "passive"))
    )
    (net (code "107") (name "Net-(D287-A)") (class "Default")
      (node (ref "D287") (pin "1") (pinfunction "A_1") (pintype "passive"))
      (node (ref "S287") (pin "1") (pinfunction "1_1") (pintype "passive"))
    )
    (net (code "108") (name "Net-(D288-A)") (class "Default")
      (node (ref "D288") (pin "1") (pinfunction "A_1") (pintype "passive"))
      (node (ref "S288") (pin "1") (pinfunction "1_1") (pintype "passive"))
    )
    (net (code "109") (name "Net-(D289-A)") (class "Default")
      (node (ref "D289") (pin "1") (pinfunction "A_1") (pintype "passive"))
      (node (ref "S289") (pin "1") (pinfunction "1_1") (pintype "passive"))
    )
    (net (code "110") (name "Net-(D290-A)") (class "Default")
      (node (ref "D290") (pin "1") (pinfunction "A_1") (pintype "passive"))
      (node (ref "S290") (pin "1") (pinfunction "1_1") (pintype "passive"))
    )
    (net (code "111") (name "Net-(D293-A)") (class "Default")
      (node (ref "D293") (pin "1") (pinfunction "A_1") (pintype "passive"))
      (node (ref "S293") (pin "1") (pinfunction "1_1") (pintype "passive"))
    )
    (net (code "112") (name "Net-(D294-A)") (class "Default")
      (node (ref "D294") (pin "1") (pinfunction "A_1") (pintype "passive"))
      (node (ref "S294") (pin "2") (pinfunction "2_2") (pintype "passive"))
      (node (ref "S294_2") (pin "1") (pinfunction "1_1") (pintype "passive"))
    )
    (net (code "113") (name "Net-(D295-A)") (class "Default")
      (node (ref "D295") (pin "1") (pinfunction "A_1") (pintype "passive"))
      (node (ref "S295") (pin "2") (pinfunction "2_2") (pintype "passive"))
      (node (ref "S295_2") (pin "1") (pinfunction "1_1") (pintype "passive"))
    )
    (net (code "114") (name "Net-(D296-A)") (class "Default")
      (node (ref "D296") (pin "1") (pinfunction "A_1") (pintype "passive"))
      (node (ref "S296") (pin "1") (pinfunction "1_1") (pintype "passive"))
      (node (ref "S296_1") (pin "1") (pinfunction "1_1") (pintype "passive"))
    )
    (net (code "115") (name "unconnected-(STAB1-Pad1)") (class "Default")
      (node (ref "STAB1") (pin "1") (pinfunction "1_1") (pintype "passive"))
    )
    (net (code "116") (name "unconnected-(STAB2-Pad1)") (class "Default")
      (node (ref "STAB2") (pin "1") (pinfunction "1_1") (pintype "passive"))
    )
    (net (code "117") (name "unconnected-(STAB3-Pad1)") (class "Default")
      (node (ref "STAB3") (pin "1") (pinfunction "1_1") (pintype "passive"))
    )
    (net (code "118") (name "unconnected-(STAB4-Pad1)") (class "Default")
      (node (ref "STAB4") (pin "1") (pinfunction "1_1") (pintype "passive"))
    )
    (net (code "119") (name "unconnected-(STAB5-Pad1)") (class "Default")
      (node (ref "STAB5") (pin "1") (pinfunction "1_1") (pintype "passive"))
    )
    (net (code "120") (name "unconnected-(STAB6-Pad1)") (class "Default")
      (node (ref "STAB6") (pin "1") (pinfunction "1_1") (pintype "passive"))
    )
    (net (code "121") (name "unconnected-(STAB8-Pad1)") (class "Default")
      (node (ref "STAB8") (pin "1") (pinfunction "1_1") (pintype "passive"))
    )
    (net (code "122") (name "unconnected-(STAB9-Pad1)") (class "Default")
      (node (ref "STAB9") (pin "1") (pinfunction "1_1") (pintype "passive"))
    )
    (net (code "123") (name "unconnected-(STAB10-Pad1)") (class "Default")
      (node (ref "STAB10") (pin "1") (pinfunction "1_1") (pintype "passive"))
    )
    (net (code "124") (name "unconnected-(STAB11-Pad1)") (class "Default")
      (node (ref "STAB11") (pin "1") (pinfunction "1_1") (pintype "passive"))
    )
  )
)
